# Filter_Board_rev1.net
KiCad netlist of a schematic drawn in EAGLE
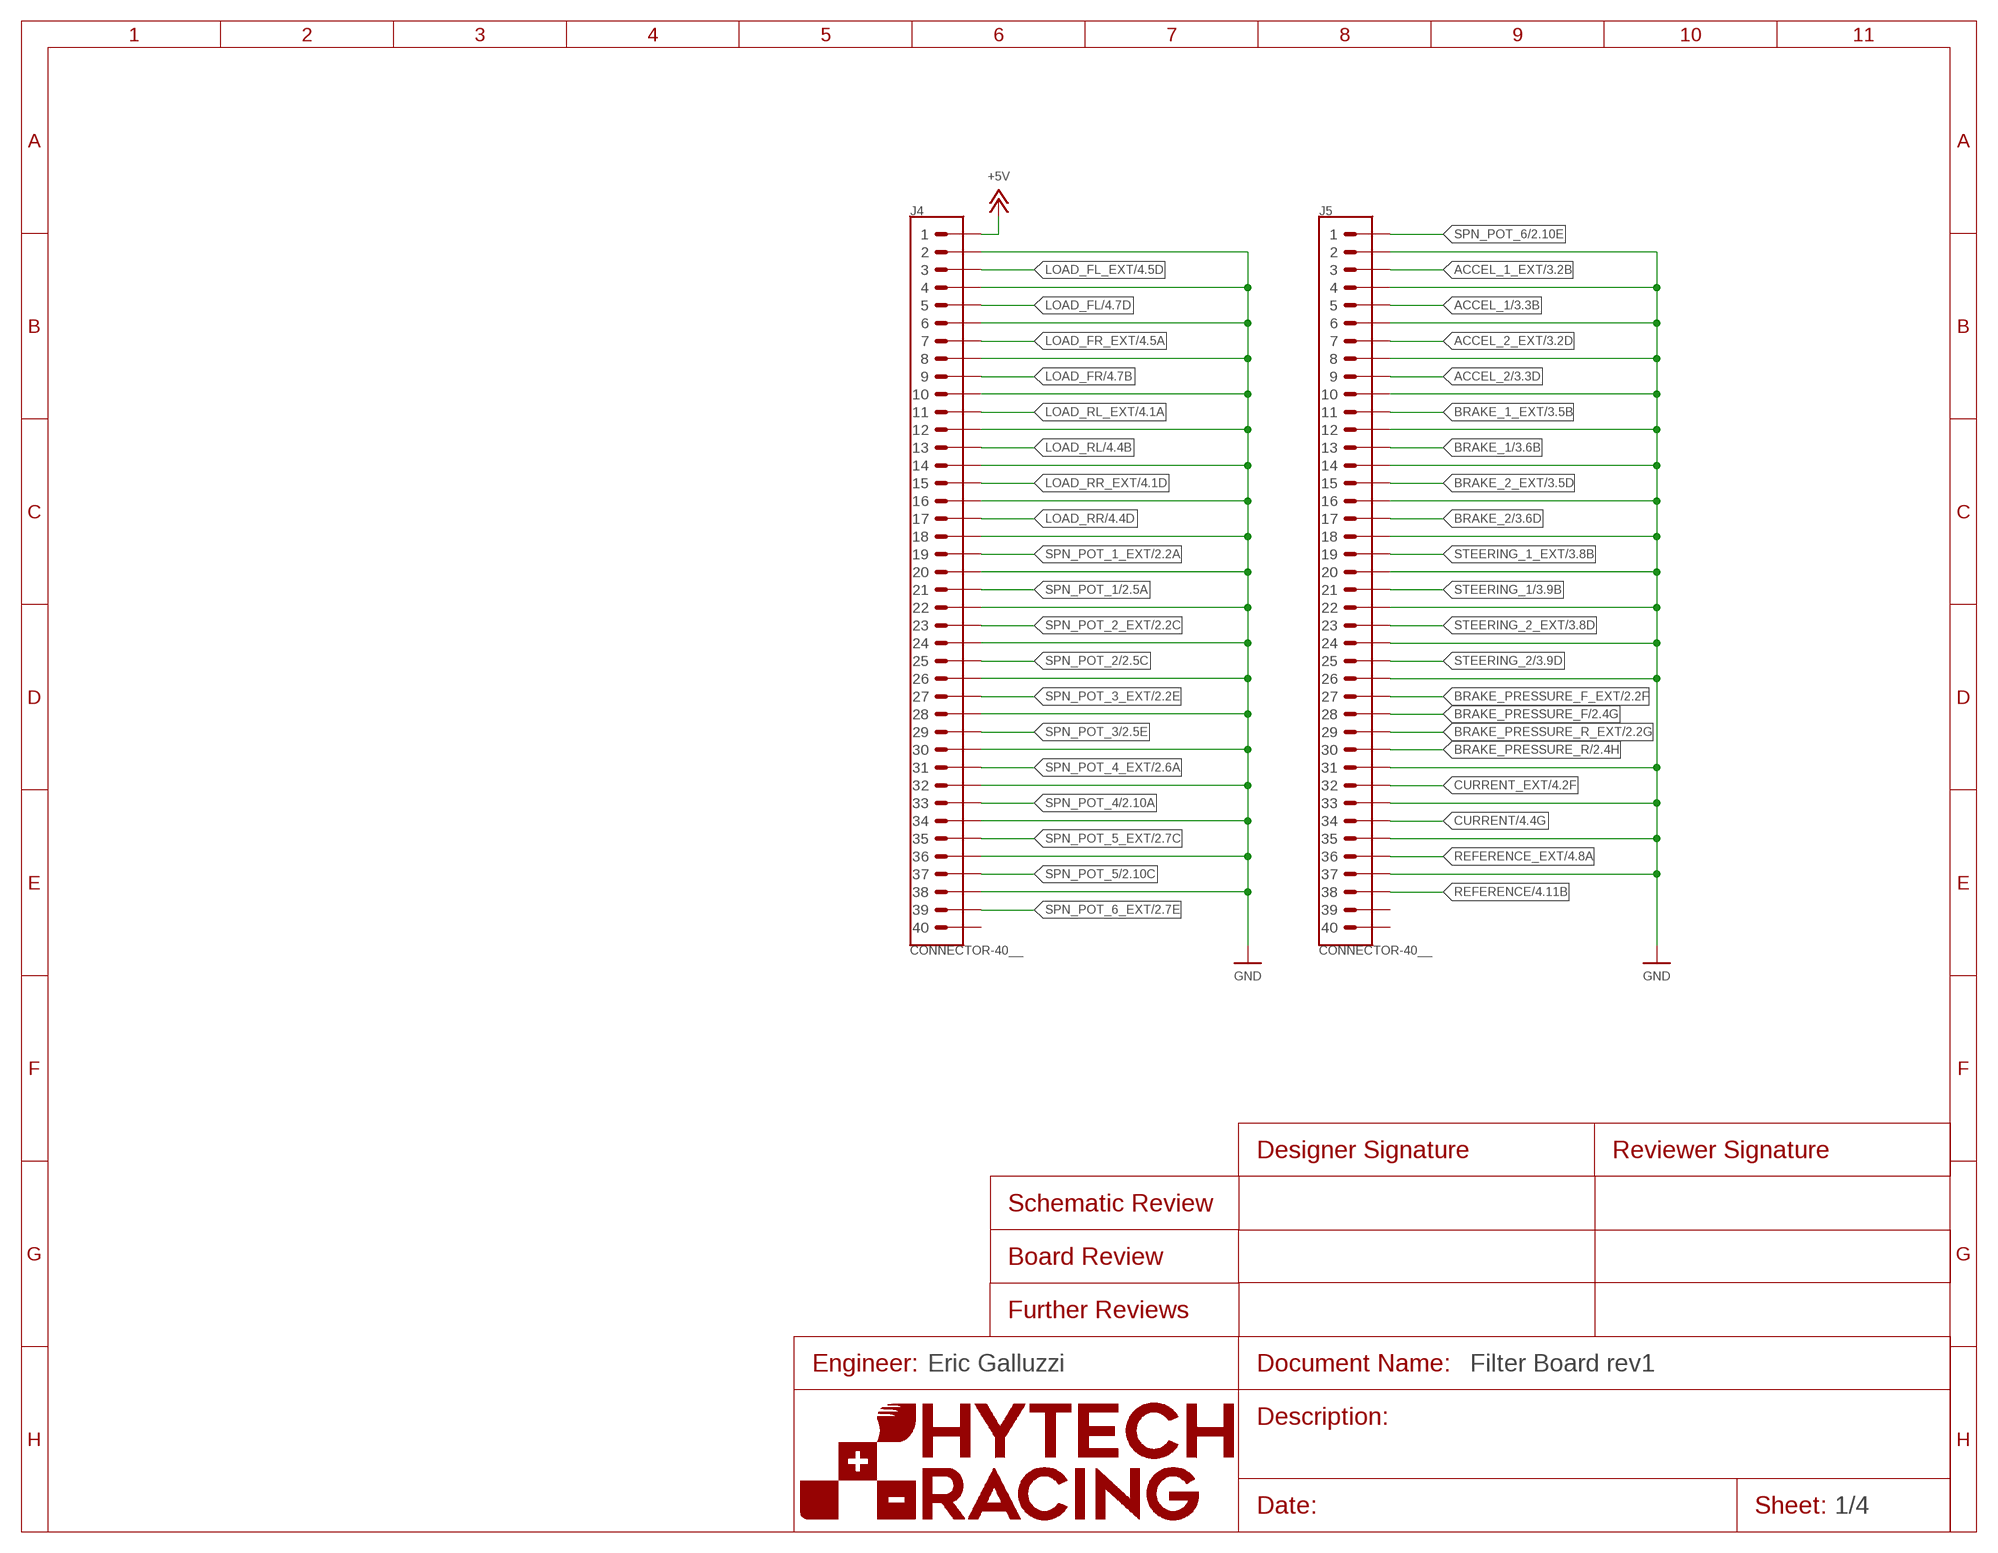
[diagram p0: schematic, sheet 1]
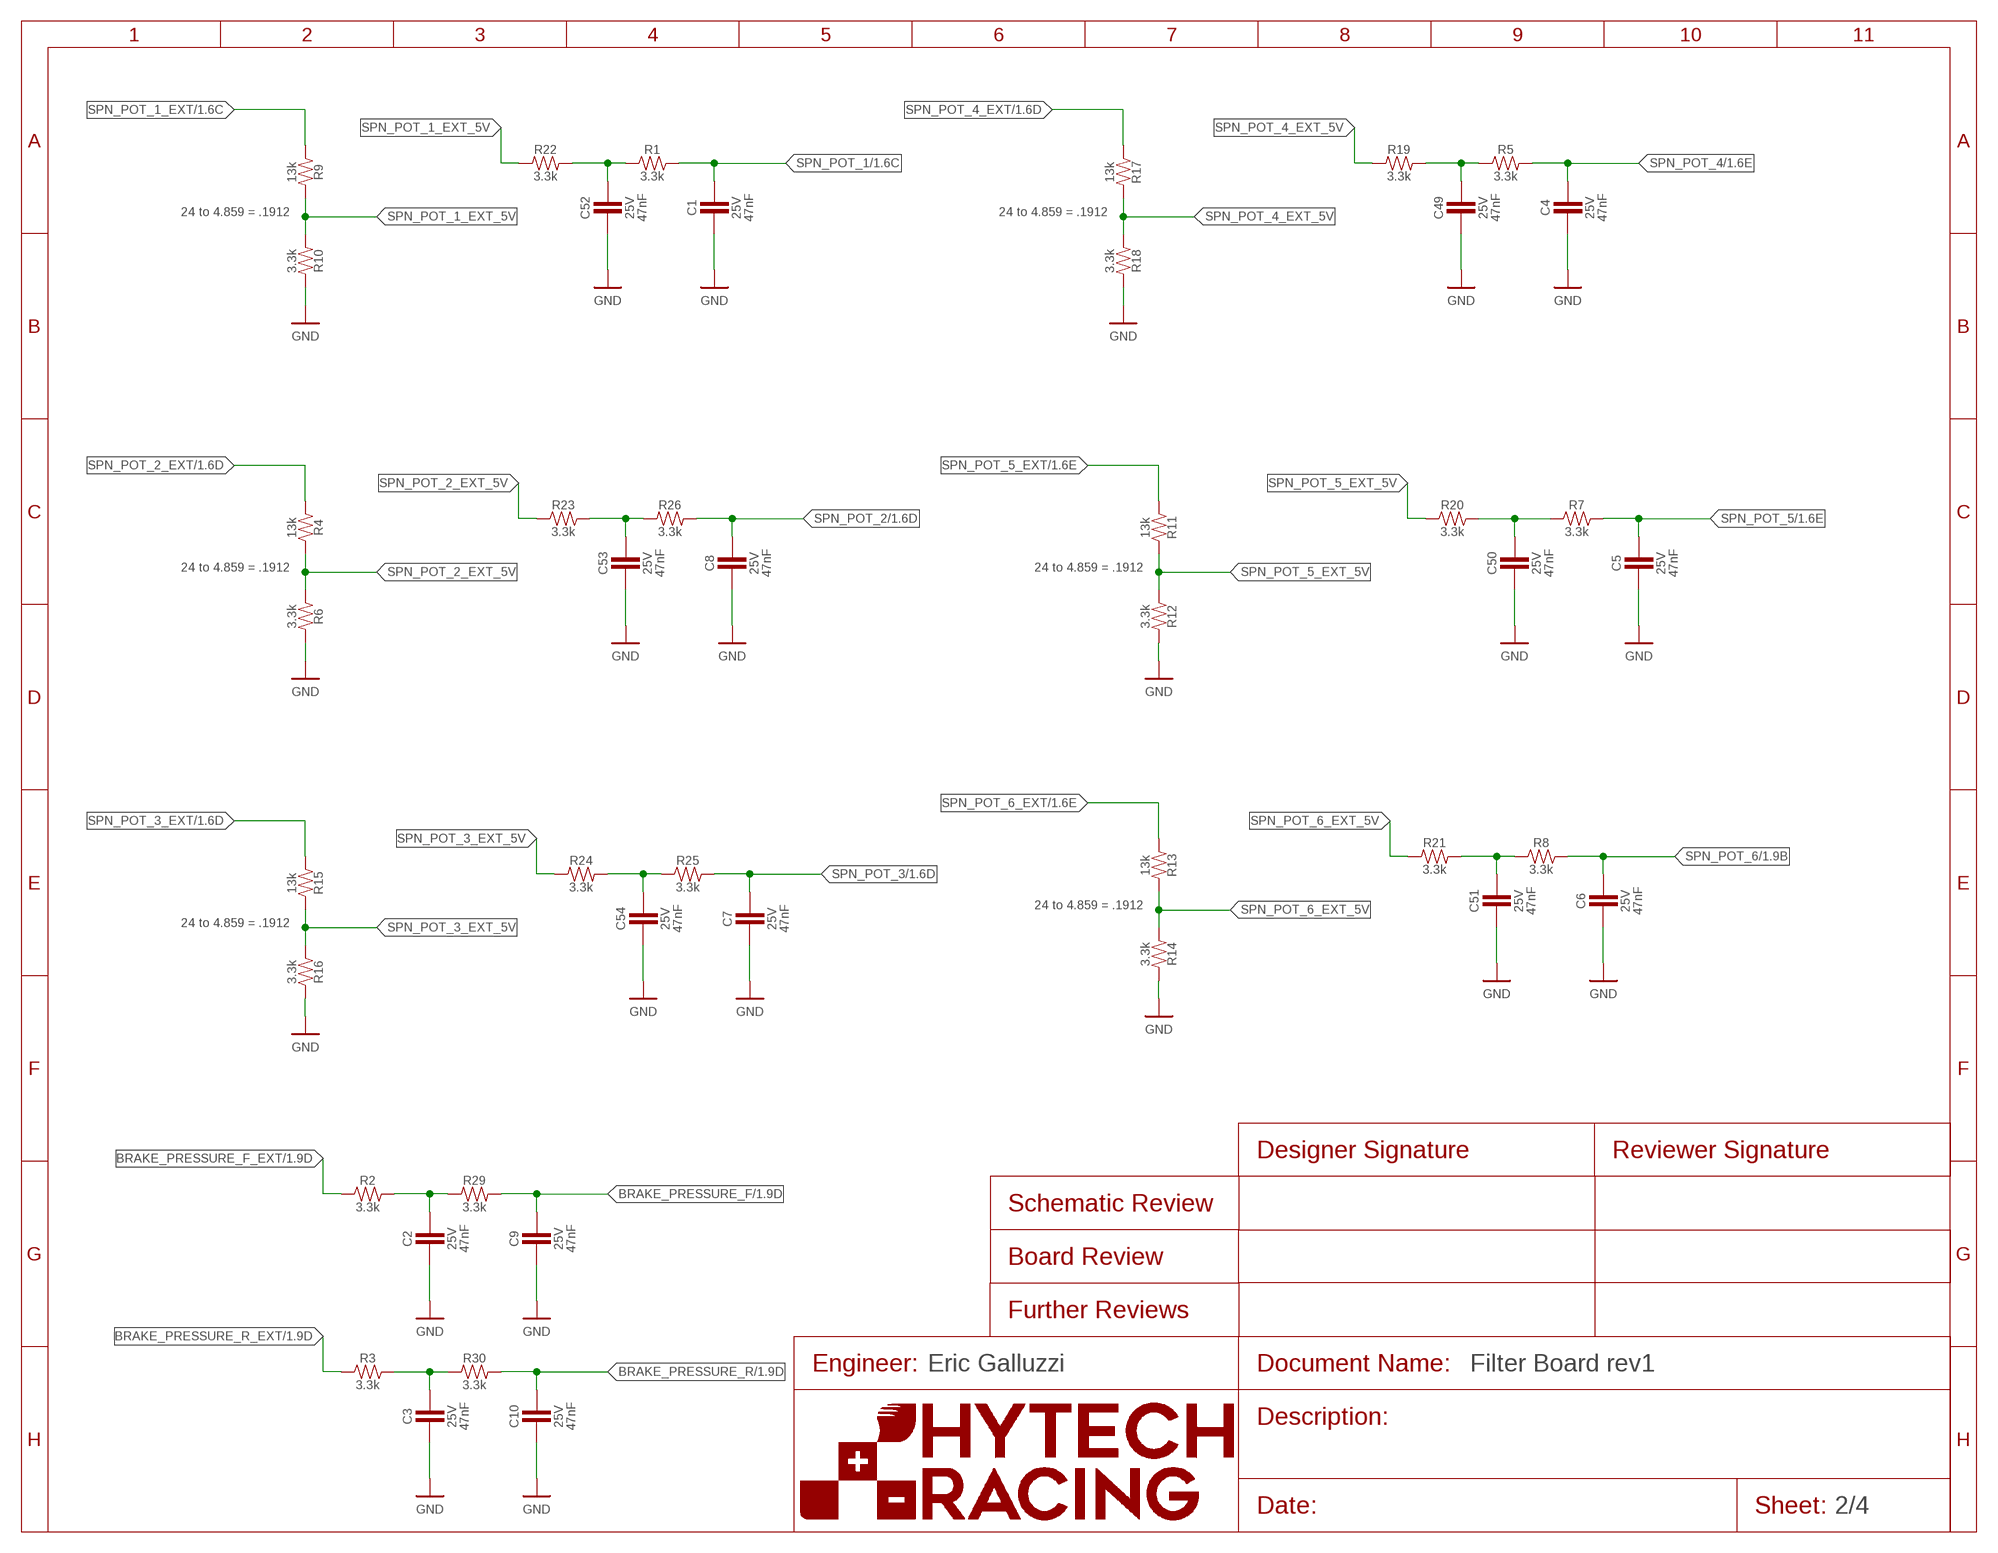
[diagram p1: schematic, sheet 2]
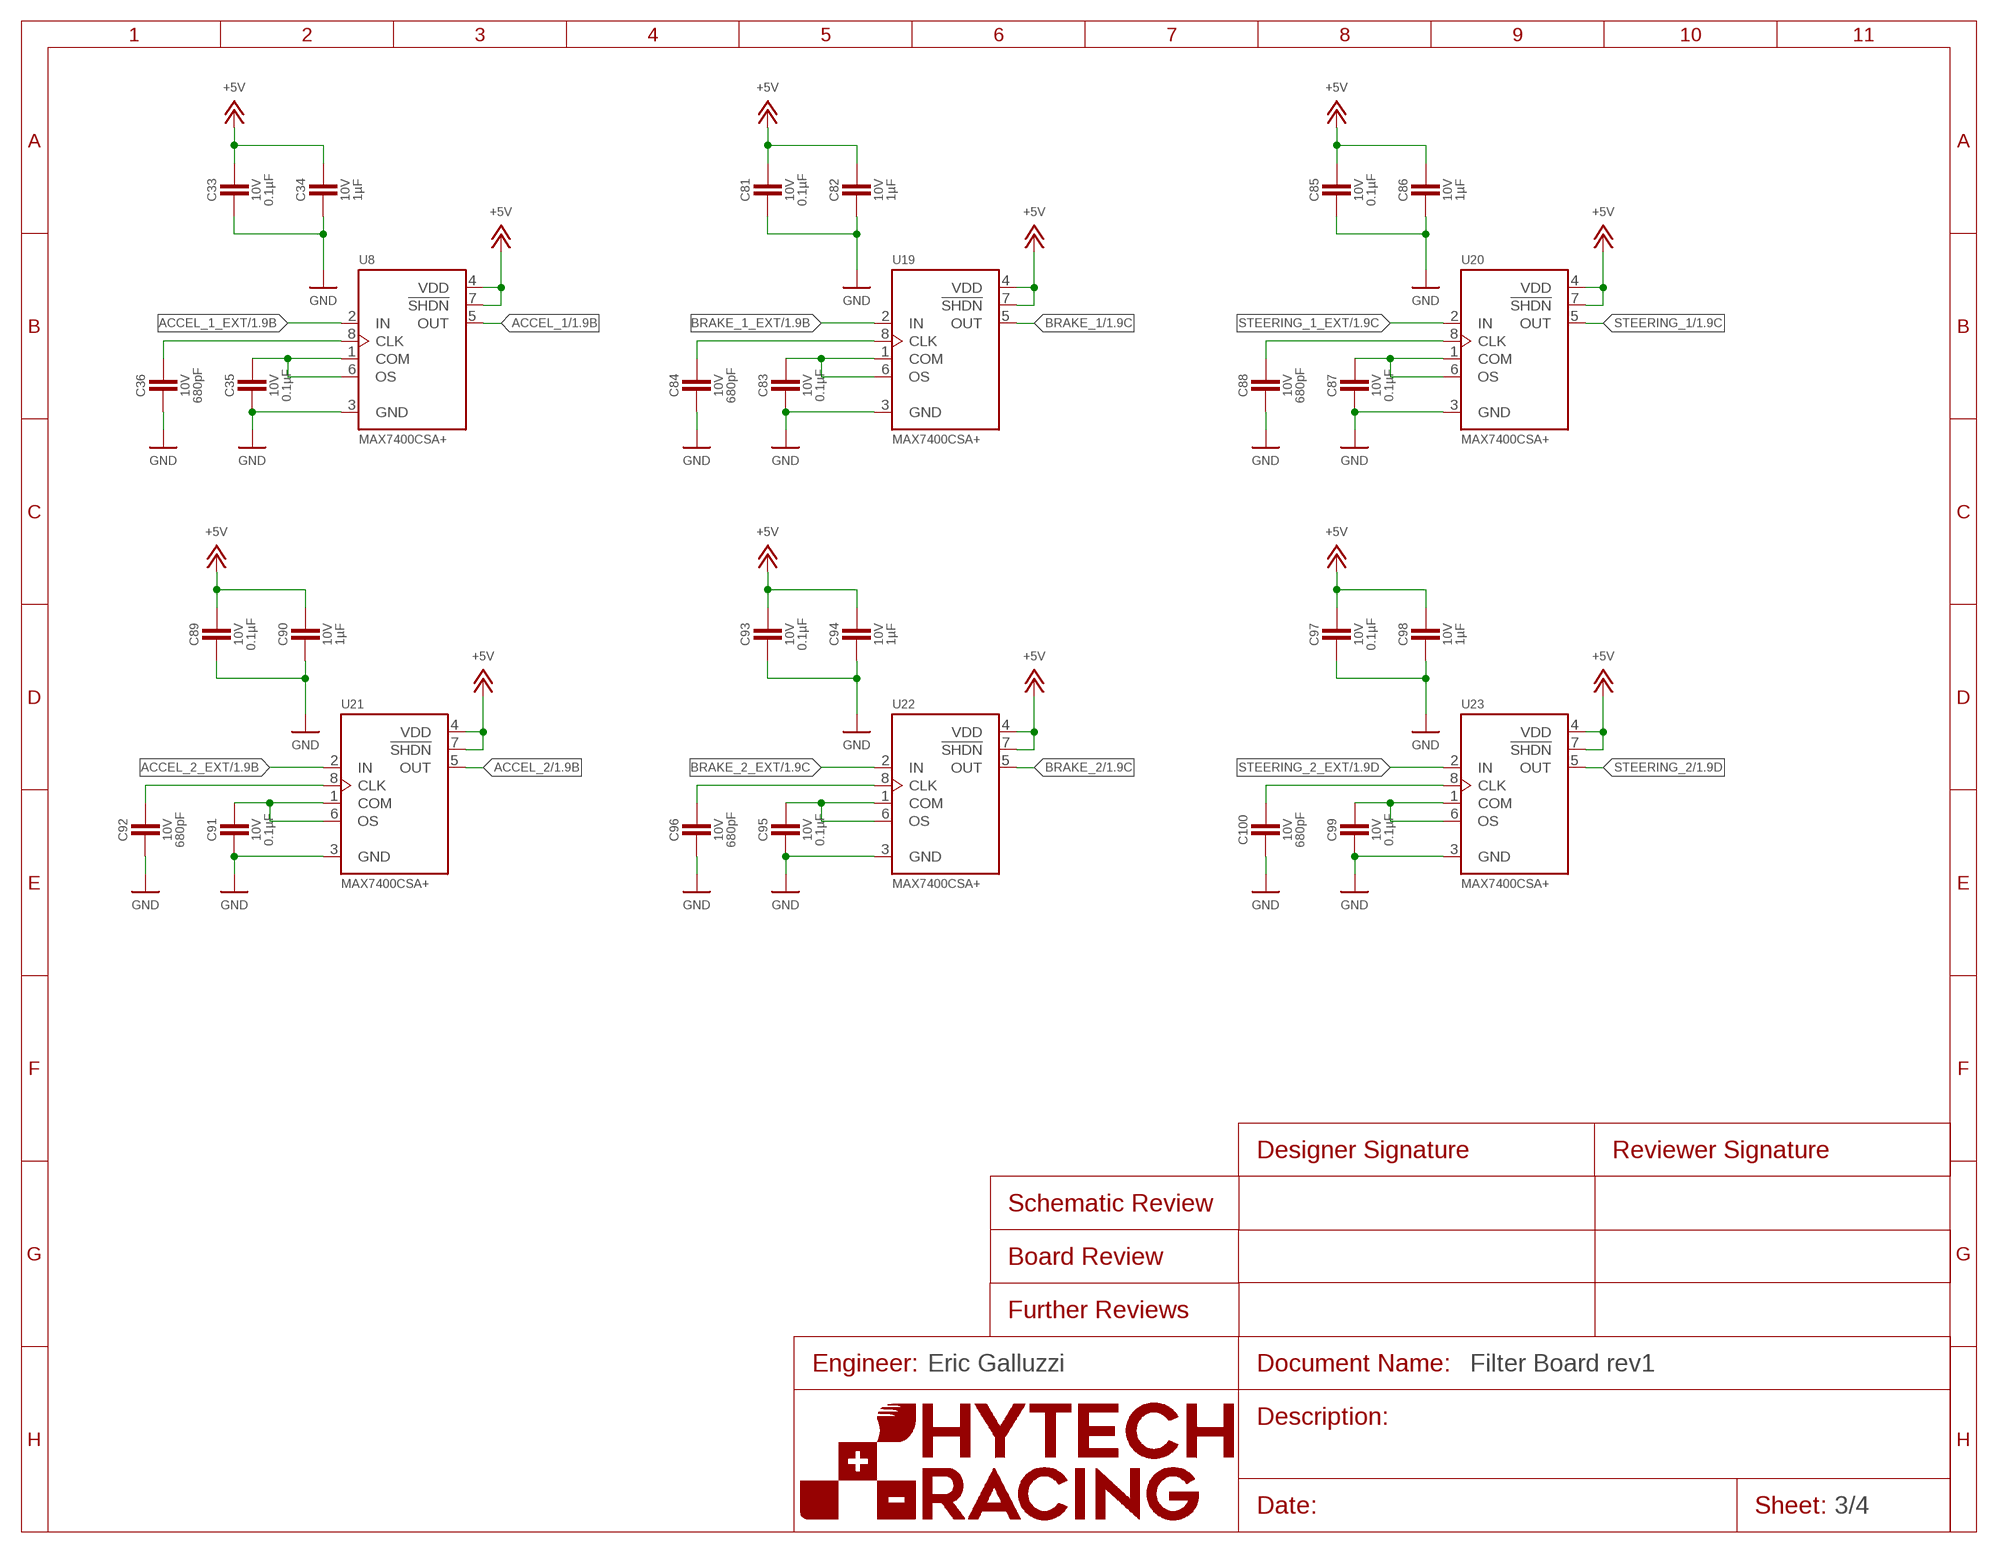
[diagram p2: schematic, sheet 3]
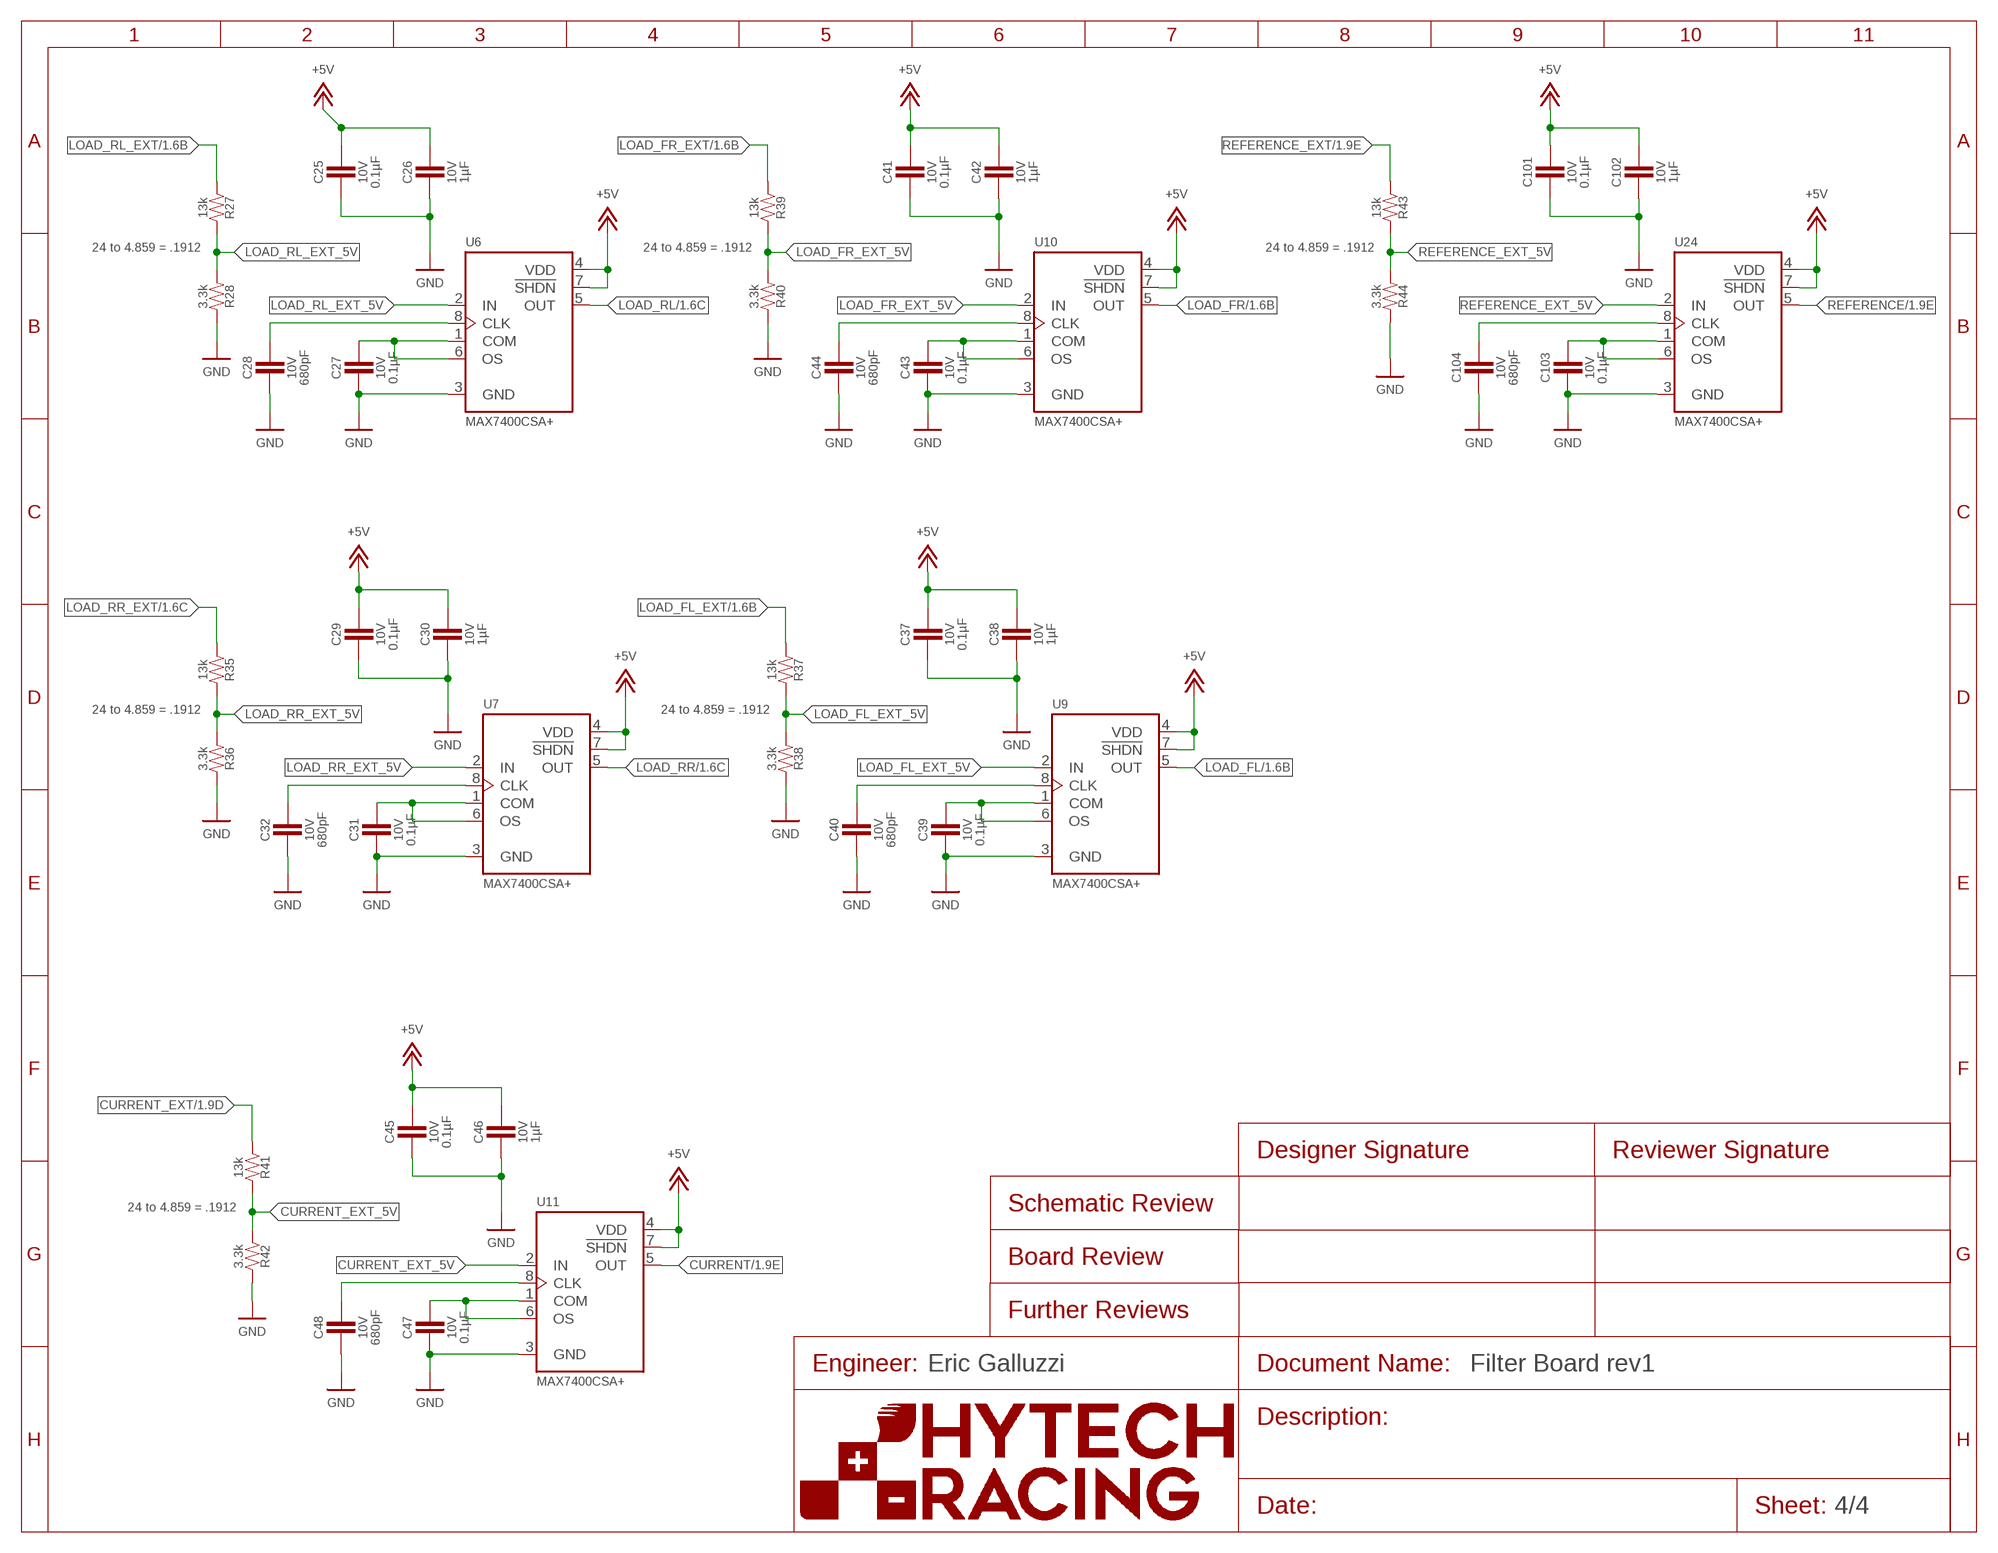
[diagram p3: schematic, sheet 4]

(export (version "E")
  (design (tool "Eeschema 10.0.6"))
  (components
    (comp (ref "C1")
      (value "CAPACITOR_0603_25V_47NF")
      (footprint "eagle-import:0603-CAP")
      (fields
        (field (name "CAPACITANCE") "47nF")
        (field (name "MANUFACTURER") "Kyocera AVX")
        (field (name "MPN") "06033C473K4Z2A")
        (field (name "TOLERANCE") "10%")
        (field (name "VOLTAGE") "25V")
      )
      (libsource (lib "eagle-import") (part "CAPACITOR_?_060325V_47NF"))
    )
    (comp (ref "C2")
      (value "CAPACITOR_0603_25V_47NF")
      (footprint "eagle-import:0603-CAP")
      (fields
        (field (name "CAPACITANCE") "47nF")
        (field (name "MANUFACTURER") "Kyocera AVX")
        (field (name "MPN") "06033C473K4Z2A")
        (field (name "TOLERANCE") "10%")
        (field (name "VOLTAGE") "25V")
      )
      (libsource (lib "eagle-import") (part "CAPACITOR_?_060325V_47NF"))
    )
    (comp (ref "C3")
      (value "CAPACITOR_0603_25V_47NF")
      (footprint "eagle-import:0603-CAP")
      (fields
        (field (name "CAPACITANCE") "47nF")
        (field (name "MANUFACTURER") "Kyocera AVX")
        (field (name "MPN") "06033C473K4Z2A")
        (field (name "TOLERANCE") "10%")
        (field (name "VOLTAGE") "25V")
      )
      (libsource (lib "eagle-import") (part "CAPACITOR_?_060325V_47NF"))
    )
    (comp (ref "C4")
      (value "CAPACITOR_0603_25V_47NF")
      (footprint "eagle-import:0603-CAP")
      (fields
        (field (name "CAPACITANCE") "47nF")
        (field (name "MANUFACTURER") "Kyocera AVX")
        (field (name "MPN") "06033C473K4Z2A")
        (field (name "TOLERANCE") "10%")
        (field (name "VOLTAGE") "25V")
      )
      (libsource (lib "eagle-import") (part "CAPACITOR_?_060325V_47NF"))
    )
    (comp (ref "C5")
      (value "CAPACITOR_0603_25V_47NF")
      (footprint "eagle-import:0603-CAP")
      (fields
        (field (name "CAPACITANCE") "47nF")
        (field (name "MANUFACTURER") "Kyocera AVX")
        (field (name "MPN") "06033C473K4Z2A")
        (field (name "TOLERANCE") "10%")
        (field (name "VOLTAGE") "25V")
      )
      (libsource (lib "eagle-import") (part "CAPACITOR_?_060325V_47NF"))
    )
    (comp (ref "C6")
      (value "CAPACITOR_0603_25V_47NF")
      (footprint "eagle-import:0603-CAP")
      (fields
        (field (name "CAPACITANCE") "47nF")
        (field (name "MANUFACTURER") "Kyocera AVX")
        (field (name "MPN") "06033C473K4Z2A")
        (field (name "TOLERANCE") "10%")
        (field (name "VOLTAGE") "25V")
      )
      (libsource (lib "eagle-import") (part "CAPACITOR_?_060325V_47NF"))
    )
    (comp (ref "C7")
      (value "CAPACITOR_0603_25V_47NF")
      (footprint "eagle-import:0603-CAP")
      (fields
        (field (name "CAPACITANCE") "47nF")
        (field (name "MANUFACTURER") "Kyocera AVX")
        (field (name "MPN") "06033C473K4Z2A")
        (field (name "TOLERANCE") "10%")
        (field (name "VOLTAGE") "25V")
      )
      (libsource (lib "eagle-import") (part "CAPACITOR_?_060325V_47NF"))
    )
    (comp (ref "C8")
      (value "CAPACITOR_0603_25V_47NF")
      (footprint "eagle-import:0603-CAP")
      (fields
        (field (name "CAPACITANCE") "47nF")
        (field (name "MANUFACTURER") "Kyocera AVX")
        (field (name "MPN") "06033C473K4Z2A")
        (field (name "TOLERANCE") "10%")
        (field (name "VOLTAGE") "25V")
      )
      (libsource (lib "eagle-import") (part "CAPACITOR_?_060325V_47NF"))
    )
    (comp (ref "C9")
      (value "CAPACITOR_0603_25V_47NF")
      (footprint "eagle-import:0603-CAP")
      (fields
        (field (name "CAPACITANCE") "47nF")
        (field (name "MANUFACTURER") "Kyocera AVX")
        (field (name "MPN") "06033C473K4Z2A")
        (field (name "TOLERANCE") "10%")
        (field (name "VOLTAGE") "25V")
      )
      (libsource (lib "eagle-import") (part "CAPACITOR_?_060325V_47NF"))
    )
    (comp (ref "C10")
      (value "CAPACITOR_0603_25V_47NF")
      (footprint "eagle-import:0603-CAP")
      (fields
        (field (name "CAPACITANCE") "47nF")
        (field (name "MANUFACTURER") "Kyocera AVX")
        (field (name "MPN") "06033C473K4Z2A")
        (field (name "TOLERANCE") "10%")
        (field (name "VOLTAGE") "25V")
      )
      (libsource (lib "eagle-import") (part "CAPACITOR_?_060325V_47NF"))
    )
    (comp (ref "C49")
      (value "CAPACITOR_0603_25V_47NF")
      (footprint "eagle-import:0603-CAP")
      (fields
        (field (name "CAPACITANCE") "47nF")
        (field (name "MANUFACTURER") "Kyocera AVX")
        (field (name "MPN") "06033C473K4Z2A")
        (field (name "TOLERANCE") "10%")
        (field (name "VOLTAGE") "25V")
      )
      (libsource (lib "eagle-import") (part "CAPACITOR_?_060325V_47NF"))
    )
    (comp (ref "C50")
      (value "CAPACITOR_0603_25V_47NF")
      (footprint "eagle-import:0603-CAP")
      (fields
        (field (name "CAPACITANCE") "47nF")
        (field (name "MANUFACTURER") "Kyocera AVX")
        (field (name "MPN") "06033C473K4Z2A")
        (field (name "TOLERANCE") "10%")
        (field (name "VOLTAGE") "25V")
      )
      (libsource (lib "eagle-import") (part "CAPACITOR_?_060325V_47NF"))
    )
    (comp (ref "C51")
      (value "CAPACITOR_0603_25V_47NF")
      (footprint "eagle-import:0603-CAP")
      (fields
        (field (name "CAPACITANCE") "47nF")
        (field (name "MANUFACTURER") "Kyocera AVX")
        (field (name "MPN") "06033C473K4Z2A")
        (field (name "TOLERANCE") "10%")
        (field (name "VOLTAGE") "25V")
      )
      (libsource (lib "eagle-import") (part "CAPACITOR_?_060325V_47NF"))
    )
    (comp (ref "C52")
      (value "CAPACITOR_0603_25V_47NF")
      (footprint "eagle-import:0603-CAP")
      (fields
        (field (name "CAPACITANCE") "47nF")
        (field (name "MANUFACTURER") "Kyocera AVX")
        (field (name "MPN") "06033C473K4Z2A")
        (field (name "TOLERANCE") "10%")
        (field (name "VOLTAGE") "25V")
      )
      (libsource (lib "eagle-import") (part "CAPACITOR_?_060325V_47NF"))
    )
    (comp (ref "C53")
      (value "CAPACITOR_0603_25V_47NF")
      (footprint "eagle-import:0603-CAP")
      (fields
        (field (name "CAPACITANCE") "47nF")
        (field (name "MANUFACTURER") "Kyocera AVX")
        (field (name "MPN") "06033C473K4Z2A")
        (field (name "TOLERANCE") "10%")
        (field (name "VOLTAGE") "25V")
      )
      (libsource (lib "eagle-import") (part "CAPACITOR_?_060325V_47NF"))
    )
    (comp (ref "C54")
      (value "CAPACITOR_0603_25V_47NF")
      (footprint "eagle-import:0603-CAP")
      (fields
        (field (name "CAPACITANCE") "47nF")
        (field (name "MANUFACTURER") "Kyocera AVX")
        (field (name "MPN") "06033C473K4Z2A")
        (field (name "TOLERANCE") "10%")
        (field (name "VOLTAGE") "25V")
      )
      (libsource (lib "eagle-import") (part "CAPACITOR_?_060325V_47NF"))
    )
    (comp (ref "R1")
      (value "RESISTOR_0603_3.3K")
      (footprint "eagle-import:0603-RES")
      (fields
        (field (name "MANUFACTURER") "Panasonic Electronic Components")
        (field (name "MPN") "ERJ-PB3D3301V")
        (field (name "POWER") "0.2W")
        (field (name "RESISTANCE") "3.3k")
      )
      (libsource (lib "eagle-import") (part "RESISTOR_?_06033.3K"))
    )
    (comp (ref "R2")
      (value "RESISTOR_0603_3.3K")
      (footprint "eagle-import:0603-RES")
      (fields
        (field (name "MANUFACTURER") "Panasonic Electronic Components")
        (field (name "MPN") "ERJ-PB3D3301V")
        (field (name "POWER") "0.2W")
        (field (name "RESISTANCE") "3.3k")
      )
      (libsource (lib "eagle-import") (part "RESISTOR_?_06033.3K"))
    )
    (comp (ref "R3")
      (value "RESISTOR_0603_3.3K")
      (footprint "eagle-import:0603-RES")
      (fields
        (field (name "MANUFACTURER") "Panasonic Electronic Components")
        (field (name "MPN") "ERJ-PB3D3301V")
        (field (name "POWER") "0.2W")
        (field (name "RESISTANCE") "3.3k")
      )
      (libsource (lib "eagle-import") (part "RESISTOR_?_06033.3K"))
    )
    (comp (ref "R4")
      (value "RESISTOR_0603_13K")
      (footprint "eagle-import:0603-RES")
      (fields
        (field (name "MANUFACTURER") "Panasonic Electronic Components")
        (field (name "MPN") "ERA-3ARW133V")
        (field (name "POWER") "0.1W")
        (field (name "RESISTANCE") "13k")
      )
      (libsource (lib "eagle-import") (part "RESISTOR_?_060313K"))
    )
    (comp (ref "R5")
      (value "RESISTOR_0603_3.3K")
      (footprint "eagle-import:0603-RES")
      (fields
        (field (name "MANUFACTURER") "Panasonic Electronic Components")
        (field (name "MPN") "ERJ-PB3D3301V")
        (field (name "POWER") "0.2W")
        (field (name "RESISTANCE") "3.3k")
      )
      (libsource (lib "eagle-import") (part "RESISTOR_?_06033.3K"))
    )
    (comp (ref "R6")
      (value "RESISTOR_0603_3.3K")
      (footprint "eagle-import:0603-RES")
      (fields
        (field (name "MANUFACTURER") "Panasonic Electronic Components")
        (field (name "MPN") "ERJ-PB3D3301V")
        (field (name "POWER") "0.2W")
        (field (name "RESISTANCE") "3.3k")
      )
      (libsource (lib "eagle-import") (part "RESISTOR_?_06033.3K"))
    )
    (comp (ref "R7")
      (value "RESISTOR_0603_3.3K")
      (footprint "eagle-import:0603-RES")
      (fields
        (field (name "MANUFACTURER") "Panasonic Electronic Components")
        (field (name "MPN") "ERJ-PB3D3301V")
        (field (name "POWER") "0.2W")
        (field (name "RESISTANCE") "3.3k")
      )
      (libsource (lib "eagle-import") (part "RESISTOR_?_06033.3K"))
    )
    (comp (ref "R8")
      (value "RESISTOR_0603_3.3K")
      (footprint "eagle-import:0603-RES")
      (fields
        (field (name "MANUFACTURER") "Panasonic Electronic Components")
        (field (name "MPN") "ERJ-PB3D3301V")
        (field (name "POWER") "0.2W")
        (field (name "RESISTANCE") "3.3k")
      )
      (libsource (lib "eagle-import") (part "RESISTOR_?_06033.3K"))
    )
    (comp (ref "R9")
      (value "RESISTOR_0603_13K")
      (footprint "eagle-import:0603-RES")
      (fields
        (field (name "MANUFACTURER") "Panasonic Electronic Components")
        (field (name "MPN") "ERA-3ARW133V")
        (field (name "POWER") "0.1W")
        (field (name "RESISTANCE") "13k")
      )
      (libsource (lib "eagle-import") (part "RESISTOR_?_060313K"))
    )
    (comp (ref "R10")
      (value "RESISTOR_0603_3.3K")
      (footprint "eagle-import:0603-RES")
      (fields
        (field (name "MANUFACTURER") "Panasonic Electronic Components")
        (field (name "MPN") "ERJ-PB3D3301V")
        (field (name "POWER") "0.2W")
        (field (name "RESISTANCE") "3.3k")
      )
      (libsource (lib "eagle-import") (part "RESISTOR_?_06033.3K"))
    )
    (comp (ref "R11")
      (value "RESISTOR_0603_13K")
      (footprint "eagle-import:0603-RES")
      (fields
        (field (name "MANUFACTURER") "Panasonic Electronic Components")
        (field (name "MPN") "ERA-3ARW133V")
        (field (name "POWER") "0.1W")
        (field (name "RESISTANCE") "13k")
      )
      (libsource (lib "eagle-import") (part "RESISTOR_?_060313K"))
    )
    (comp (ref "R12")
      (value "RESISTOR_0603_3.3K")
      (footprint "eagle-import:0603-RES")
      (fields
        (field (name "MANUFACTURER") "Panasonic Electronic Components")
        (field (name "MPN") "ERJ-PB3D3301V")
        (field (name "POWER") "0.2W")
        (field (name "RESISTANCE") "3.3k")
      )
      (libsource (lib "eagle-import") (part "RESISTOR_?_06033.3K"))
    )
    (comp (ref "R13")
      (value "RESISTOR_0603_13K")
      (footprint "eagle-import:0603-RES")
      (fields
        (field (name "MANUFACTURER") "Panasonic Electronic Components")
        (field (name "MPN") "ERA-3ARW133V")
        (field (name "POWER") "0.1W")
        (field (name "RESISTANCE") "13k")
      )
      (libsource (lib "eagle-import") (part "RESISTOR_?_060313K"))
    )
    (comp (ref "R14")
      (value "RESISTOR_0603_3.3K")
      (footprint "eagle-import:0603-RES")
      (fields
        (field (name "MANUFACTURER") "Panasonic Electronic Components")
        (field (name "MPN") "ERJ-PB3D3301V")
        (field (name "POWER") "0.2W")
        (field (name "RESISTANCE") "3.3k")
      )
      (libsource (lib "eagle-import") (part "RESISTOR_?_06033.3K"))
    )
    (comp (ref "R15")
      (value "RESISTOR_0603_13K")
      (footprint "eagle-import:0603-RES")
      (fields
        (field (name "MANUFACTURER") "Panasonic Electronic Components")
        (field (name "MPN") "ERA-3ARW133V")
        (field (name "POWER") "0.1W")
        (field (name "RESISTANCE") "13k")
      )
      (libsource (lib "eagle-import") (part "RESISTOR_?_060313K"))
    )
    (comp (ref "R16")
      (value "RESISTOR_0603_3.3K")
      (footprint "eagle-import:0603-RES")
      (fields
        (field (name "MANUFACTURER") "Panasonic Electronic Components")
        (field (name "MPN") "ERJ-PB3D3301V")
        (field (name "POWER") "0.2W")
        (field (name "RESISTANCE") "3.3k")
      )
      (libsource (lib "eagle-import") (part "RESISTOR_?_06033.3K"))
    )
    (comp (ref "R17")
      (value "RESISTOR_0603_13K")
      (footprint "eagle-import:0603-RES")
      (fields
        (field (name "MANUFACTURER") "Panasonic Electronic Components")
        (field (name "MPN") "ERA-3ARW133V")
        (field (name "POWER") "0.1W")
        (field (name "RESISTANCE") "13k")
      )
      (libsource (lib "eagle-import") (part "RESISTOR_?_060313K"))
    )
    (comp (ref "R18")
      (value "RESISTOR_0603_3.3K")
      (footprint "eagle-import:0603-RES")
      (fields
        (field (name "MANUFACTURER") "Panasonic Electronic Components")
        (field (name "MPN") "ERJ-PB3D3301V")
        (field (name "POWER") "0.2W")
        (field (name "RESISTANCE") "3.3k")
      )
      (libsource (lib "eagle-import") (part "RESISTOR_?_06033.3K"))
    )
    (comp (ref "R19")
      (value "RESISTOR_0603_3.3K")
      (footprint "eagle-import:0603-RES")
      (fields
        (field (name "MANUFACTURER") "Panasonic Electronic Components")
        (field (name "MPN") "ERJ-PB3D3301V")
        (field (name "POWER") "0.2W")
        (field (name "RESISTANCE") "3.3k")
      )
      (libsource (lib "eagle-import") (part "RESISTOR_?_06033.3K"))
    )
    (comp (ref "R20")
      (value "RESISTOR_0603_3.3K")
      (footprint "eagle-import:0603-RES")
      (fields
        (field (name "MANUFACTURER") "Panasonic Electronic Components")
        (field (name "MPN") "ERJ-PB3D3301V")
        (field (name "POWER") "0.2W")
        (field (name "RESISTANCE") "3.3k")
      )
      (libsource (lib "eagle-import") (part "RESISTOR_?_06033.3K"))
    )
    (comp (ref "R21")
      (value "RESISTOR_0603_3.3K")
      (footprint "eagle-import:0603-RES")
      (fields
        (field (name "MANUFACTURER") "Panasonic Electronic Components")
        (field (name "MPN") "ERJ-PB3D3301V")
        (field (name "POWER") "0.2W")
        (field (name "RESISTANCE") "3.3k")
      )
      (libsource (lib "eagle-import") (part "RESISTOR_?_06033.3K"))
    )
    (comp (ref "R22")
      (value "RESISTOR_0603_3.3K")
      (footprint "eagle-import:0603-RES")
      (fields
        (field (name "MANUFACTURER") "Panasonic Electronic Components")
        (field (name "MPN") "ERJ-PB3D3301V")
        (field (name "POWER") "0.2W")
        (field (name "RESISTANCE") "3.3k")
      )
      (libsource (lib "eagle-import") (part "RESISTOR_?_06033.3K"))
    )
    (comp (ref "R23")
      (value "RESISTOR_0603_3.3K")
      (footprint "eagle-import:0603-RES")
      (fields
        (field (name "MANUFACTURER") "Panasonic Electronic Components")
        (field (name "MPN") "ERJ-PB3D3301V")
        (field (name "POWER") "0.2W")
        (field (name "RESISTANCE") "3.3k")
      )
      (libsource (lib "eagle-import") (part "RESISTOR_?_06033.3K"))
    )
    (comp (ref "R24")
      (value "RESISTOR_0603_3.3K")
      (footprint "eagle-import:0603-RES")
      (fields
        (field (name "MANUFACTURER") "Panasonic Electronic Components")
        (field (name "MPN") "ERJ-PB3D3301V")
        (field (name "POWER") "0.2W")
        (field (name "RESISTANCE") "3.3k")
      )
      (libsource (lib "eagle-import") (part "RESISTOR_?_06033.3K"))
    )
    (comp (ref "R25")
      (value "RESISTOR_0603_3.3K")
      (footprint "eagle-import:0603-RES")
      (fields
        (field (name "MANUFACTURER") "Panasonic Electronic Components")
        (field (name "MPN") "ERJ-PB3D3301V")
        (field (name "POWER") "0.2W")
        (field (name "RESISTANCE") "3.3k")
      )
      (libsource (lib "eagle-import") (part "RESISTOR_?_06033.3K"))
    )
    (comp (ref "R26")
      (value "RESISTOR_0603_3.3K")
      (footprint "eagle-import:0603-RES")
      (fields
        (field (name "MANUFACTURER") "Panasonic Electronic Components")
        (field (name "MPN") "ERJ-PB3D3301V")
        (field (name "POWER") "0.2W")
        (field (name "RESISTANCE") "3.3k")
      )
      (libsource (lib "eagle-import") (part "RESISTOR_?_06033.3K"))
    )
    (comp (ref "R29")
      (value "RESISTOR_0603_3.3K")
      (footprint "eagle-import:0603-RES")
      (fields
        (field (name "MANUFACTURER") "Panasonic Electronic Components")
        (field (name "MPN") "ERJ-PB3D3301V")
        (field (name "POWER") "0.2W")
        (field (name "RESISTANCE") "3.3k")
      )
      (libsource (lib "eagle-import") (part "RESISTOR_?_06033.3K"))
    )
    (comp (ref "R30")
      (value "RESISTOR_0603_3.3K")
      (footprint "eagle-import:0603-RES")
      (fields
        (field (name "MANUFACTURER") "Panasonic Electronic Components")
        (field (name "MPN") "ERJ-PB3D3301V")
        (field (name "POWER") "0.2W")
        (field (name "RESISTANCE") "3.3k")
      )
      (libsource (lib "eagle-import") (part "RESISTOR_?_06033.3K"))
    )
    (comp (ref "J4")
      (value "CONNECTOR-40__")
      (footprint "eagle-import:EHT-120-01")
      (fields (field (name "MANUFACTURER") "Samtec") (field (name "MPN") "EHT-120-01-S-D"))
      (libsource (lib "eagle-import") (part "CONNECTOR-40_?_"))
    )
    (comp (ref "J5")
      (value "CONNECTOR-40__")
      (footprint "eagle-import:EHT-120-01")
      (fields (field (name "MANUFACTURER") "Samtec") (field (name "MPN") "EHT-120-01-S-D"))
      (libsource (lib "eagle-import") (part "CONNECTOR-40_?_"))
    )
    (comp (ref "C33")
      (value "CAPACITOR_0603_10V_0.1UF")
      (footprint "eagle-import:0603-CAP")
      (fields
        (field (name "CAPACITANCE") "0.1µF")
        (field (name "MANUFACTURER") "Vishay Vitramon")
        (field (name "MPN") "VJ0603Y104JXQPW1BC")
        (field (name "TOLERANCE") "5%")
        (field (name "VOLTAGE") "10V")
      )
      (libsource (lib "eagle-import") (part "CAPACITOR_?_060310V_0.1UF"))
    )
    (comp (ref "C34")
      (value "CAPACITOR_0603_10V_1UF")
      (footprint "eagle-import:0603-CAP")
      (fields
        (field (name "CAPACITANCE") "1µF")
        (field (name "MANUFACTURER") "Yageo")
        (field (name "MPN") "CC0603KRX7R6BB105")
        (field (name "TOLERANCE") "10%")
        (field (name "VOLTAGE") "10V")
      )
      (libsource (lib "eagle-import") (part "CAPACITOR_?_060310V_1UF"))
    )
    (comp (ref "C35")
      (value "CAPACITOR_0603_10V_0.1UF")
      (footprint "eagle-import:0603-CAP")
      (fields
        (field (name "CAPACITANCE") "0.1µF")
        (field (name "MANUFACTURER") "Vishay Vitramon")
        (field (name "MPN") "VJ0603Y104JXQPW1BC")
        (field (name "TOLERANCE") "5%")
        (field (name "VOLTAGE") "10V")
      )
      (libsource (lib "eagle-import") (part "CAPACITOR_?_060310V_0.1UF"))
    )
    (comp (ref "C36")
      (value "CAPACITOR_0603_10V_680PF")
      (footprint "eagle-import:0603-CAP")
      (fields
        (field (name "CAPACITANCE") "680pF")
        (field (name "MANUFACTURER") "Würth Elektronik")
        (field (name "MPN") "885012006013")
        (field (name "TOLERANCE") "5%")
        (field (name "VOLTAGE") "10V")
      )
      (libsource (lib "eagle-import") (part "CAPACITOR_?_060310V_680PF"))
    )
    (comp (ref "C81")
      (value "CAPACITOR_0603_10V_0.1UF")
      (footprint "eagle-import:0603-CAP")
      (fields
        (field (name "CAPACITANCE") "0.1µF")
        (field (name "MANUFACTURER") "Vishay Vitramon")
        (field (name "MPN") "VJ0603Y104JXQPW1BC")
        (field (name "TOLERANCE") "5%")
        (field (name "VOLTAGE") "10V")
      )
      (libsource (lib "eagle-import") (part "CAPACITOR_?_060310V_0.1UF"))
    )
    (comp (ref "C82")
      (value "CAPACITOR_0603_10V_1UF")
      (footprint "eagle-import:0603-CAP")
      (fields
        (field (name "CAPACITANCE") "1µF")
        (field (name "MANUFACTURER") "Yageo")
        (field (name "MPN") "CC0603KRX7R6BB105")
        (field (name "TOLERANCE") "10%")
        (field (name "VOLTAGE") "10V")
      )
      (libsource (lib "eagle-import") (part "CAPACITOR_?_060310V_1UF"))
    )
    (comp (ref "C83")
      (value "CAPACITOR_0603_10V_0.1UF")
      (footprint "eagle-import:0603-CAP")
      (fields
        (field (name "CAPACITANCE") "0.1µF")
        (field (name "MANUFACTURER") "Vishay Vitramon")
        (field (name "MPN") "VJ0603Y104JXQPW1BC")
        (field (name "TOLERANCE") "5%")
        (field (name "VOLTAGE") "10V")
      )
      (libsource (lib "eagle-import") (part "CAPACITOR_?_060310V_0.1UF"))
    )
    (comp (ref "C84")
      (value "CAPACITOR_0603_10V_680PF")
      (footprint "eagle-import:0603-CAP")
      (fields
        (field (name "CAPACITANCE") "680pF")
        (field (name "MANUFACTURER") "Würth Elektronik")
        (field (name "MPN") "885012006013")
        (field (name "TOLERANCE") "5%")
        (field (name "VOLTAGE") "10V")
      )
      (libsource (lib "eagle-import") (part "CAPACITOR_?_060310V_680PF"))
    )
    (comp (ref "C85")
      (value "CAPACITOR_0603_10V_0.1UF")
      (footprint "eagle-import:0603-CAP")
      (fields
        (field (name "CAPACITANCE") "0.1µF")
        (field (name "MANUFACTURER") "Vishay Vitramon")
        (field (name "MPN") "VJ0603Y104JXQPW1BC")
        (field (name "TOLERANCE") "5%")
        (field (name "VOLTAGE") "10V")
      )
      (libsource (lib "eagle-import") (part "CAPACITOR_?_060310V_0.1UF"))
    )
    (comp (ref "C86")
      (value "CAPACITOR_0603_10V_1UF")
      (footprint "eagle-import:0603-CAP")
      (fields
        (field (name "CAPACITANCE") "1µF")
        (field (name "MANUFACTURER") "Yageo")
        (field (name "MPN") "CC0603KRX7R6BB105")
        (field (name "TOLERANCE") "10%")
        (field (name "VOLTAGE") "10V")
      )
      (libsource (lib "eagle-import") (part "CAPACITOR_?_060310V_1UF"))
    )
    (comp (ref "C87")
      (value "CAPACITOR_0603_10V_0.1UF")
      (footprint "eagle-import:0603-CAP")
      (fields
        (field (name "CAPACITANCE") "0.1µF")
        (field (name "MANUFACTURER") "Vishay Vitramon")
        (field (name "MPN") "VJ0603Y104JXQPW1BC")
        (field (name "TOLERANCE") "5%")
        (field (name "VOLTAGE") "10V")
      )
      (libsource (lib "eagle-import") (part "CAPACITOR_?_060310V_0.1UF"))
    )
    (comp (ref "C88")
      (value "CAPACITOR_0603_10V_680PF")
      (footprint "eagle-import:0603-CAP")
      (fields
        (field (name "CAPACITANCE") "680pF")
        (field (name "MANUFACTURER") "Würth Elektronik")
        (field (name "MPN") "885012006013")
        (field (name "TOLERANCE") "5%")
        (field (name "VOLTAGE") "10V")
      )
      (libsource (lib "eagle-import") (part "CAPACITOR_?_060310V_680PF"))
    )
    (comp (ref "C89")
      (value "CAPACITOR_0603_10V_0.1UF")
      (footprint "eagle-import:0603-CAP")
      (fields
        (field (name "CAPACITANCE") "0.1µF")
        (field (name "MANUFACTURER") "Vishay Vitramon")
        (field (name "MPN") "VJ0603Y104JXQPW1BC")
        (field (name "TOLERANCE") "5%")
        (field (name "VOLTAGE") "10V")
      )
      (libsource (lib "eagle-import") (part "CAPACITOR_?_060310V_0.1UF"))
    )
    (comp (ref "C90")
      (value "CAPACITOR_0603_10V_1UF")
      (footprint "eagle-import:0603-CAP")
      (fields
        (field (name "CAPACITANCE") "1µF")
        (field (name "MANUFACTURER") "Yageo")
        (field (name "MPN") "CC0603KRX7R6BB105")
        (field (name "TOLERANCE") "10%")
        (field (name "VOLTAGE") "10V")
      )
      (libsource (lib "eagle-import") (part "CAPACITOR_?_060310V_1UF"))
    )
    (comp (ref "C91")
      (value "CAPACITOR_0603_10V_0.1UF")
      (footprint "eagle-import:0603-CAP")
      (fields
        (field (name "CAPACITANCE") "0.1µF")
        (field (name "MANUFACTURER") "Vishay Vitramon")
        (field (name "MPN") "VJ0603Y104JXQPW1BC")
        (field (name "TOLERANCE") "5%")
        (field (name "VOLTAGE") "10V")
      )
      (libsource (lib "eagle-import") (part "CAPACITOR_?_060310V_0.1UF"))
    )
    (comp (ref "C92")
      (value "CAPACITOR_0603_10V_680PF")
      (footprint "eagle-import:0603-CAP")
      (fields
        (field (name "CAPACITANCE") "680pF")
        (field (name "MANUFACTURER") "Würth Elektronik")
        (field (name "MPN") "885012006013")
        (field (name "TOLERANCE") "5%")
        (field (name "VOLTAGE") "10V")
      )
      (libsource (lib "eagle-import") (part "CAPACITOR_?_060310V_680PF"))
    )
    (comp (ref "C93")
      (value "CAPACITOR_0603_10V_0.1UF")
      (footprint "eagle-import:0603-CAP")
      (fields
        (field (name "CAPACITANCE") "0.1µF")
        (field (name "MANUFACTURER") "Vishay Vitramon")
        (field (name "MPN") "VJ0603Y104JXQPW1BC")
        (field (name "TOLERANCE") "5%")
        (field (name "VOLTAGE") "10V")
      )
      (libsource (lib "eagle-import") (part "CAPACITOR_?_060310V_0.1UF"))
    )
    (comp (ref "C94")
      (value "CAPACITOR_0603_10V_1UF")
      (footprint "eagle-import:0603-CAP")
      (fields
        (field (name "CAPACITANCE") "1µF")
        (field (name "MANUFACTURER") "Yageo")
        (field (name "MPN") "CC0603KRX7R6BB105")
        (field (name "TOLERANCE") "10%")
        (field (name "VOLTAGE") "10V")
      )
      (libsource (lib "eagle-import") (part "CAPACITOR_?_060310V_1UF"))
    )
    (comp (ref "C95")
      (value "CAPACITOR_0603_10V_0.1UF")
      (footprint "eagle-import:0603-CAP")
      (fields
        (field (name "CAPACITANCE") "0.1µF")
        (field (name "MANUFACTURER") "Vishay Vitramon")
        (field (name "MPN") "VJ0603Y104JXQPW1BC")
        (field (name "TOLERANCE") "5%")
        (field (name "VOLTAGE") "10V")
      )
      (libsource (lib "eagle-import") (part "CAPACITOR_?_060310V_0.1UF"))
    )
    (comp (ref "C96")
      (value "CAPACITOR_0603_10V_680PF")
      (footprint "eagle-import:0603-CAP")
      (fields
        (field (name "CAPACITANCE") "680pF")
        (field (name "MANUFACTURER") "Würth Elektronik")
        (field (name "MPN") "885012006013")
        (field (name "TOLERANCE") "5%")
        (field (name "VOLTAGE") "10V")
      )
      (libsource (lib "eagle-import") (part "CAPACITOR_?_060310V_680PF"))
    )
    (comp (ref "C97")
      (value "CAPACITOR_0603_10V_0.1UF")
      (footprint "eagle-import:0603-CAP")
      (fields
        (field (name "CAPACITANCE") "0.1µF")
        (field (name "MANUFACTURER") "Vishay Vitramon")
        (field (name "MPN") "VJ0603Y104JXQPW1BC")
        (field (name "TOLERANCE") "5%")
        (field (name "VOLTAGE") "10V")
      )
      (libsource (lib "eagle-import") (part "CAPACITOR_?_060310V_0.1UF"))
    )
    (comp (ref "C98")
      (value "CAPACITOR_0603_10V_1UF")
      (footprint "eagle-import:0603-CAP")
      (fields
        (field (name "CAPACITANCE") "1µF")
        (field (name "MANUFACTURER") "Yageo")
        (field (name "MPN") "CC0603KRX7R6BB105")
        (field (name "TOLERANCE") "10%")
        (field (name "VOLTAGE") "10V")
      )
      (libsource (lib "eagle-import") (part "CAPACITOR_?_060310V_1UF"))
    )
    (comp (ref "C99")
      (value "CAPACITOR_0603_10V_0.1UF")
      (footprint "eagle-import:0603-CAP")
      (fields
        (field (name "CAPACITANCE") "0.1µF")
        (field (name "MANUFACTURER") "Vishay Vitramon")
        (field (name "MPN") "VJ0603Y104JXQPW1BC")
        (field (name "TOLERANCE") "5%")
        (field (name "VOLTAGE") "10V")
      )
      (libsource (lib "eagle-import") (part "CAPACITOR_?_060310V_0.1UF"))
    )
    (comp (ref "C100")
      (value "CAPACITOR_0603_10V_680PF")
      (footprint "eagle-import:0603-CAP")
      (fields
        (field (name "CAPACITANCE") "680pF")
        (field (name "MANUFACTURER") "Würth Elektronik")
        (field (name "MPN") "885012006013")
        (field (name "TOLERANCE") "5%")
        (field (name "VOLTAGE") "10V")
      )
      (libsource (lib "eagle-import") (part "CAPACITOR_?_060310V_680PF"))
    )
    (comp (ref "U8")
      (value "MAX7400")
      (footprint "eagle-import:SOIC-08(NARROW,0.15_)")
      (fields (field (name "MANUFACTURER") "Maxim Integrated") (field (name "MPN") "MAX7400CSA+"))
      (libsource (lib "eagle-import") (part "MAX7400"))
    )
    (comp (ref "U19")
      (value "MAX7400")
      (footprint "eagle-import:SOIC-08(NARROW,0.15_)")
      (fields (field (name "MANUFACTURER") "Maxim Integrated") (field (name "MPN") "MAX7400CSA+"))
      (libsource (lib "eagle-import") (part "MAX7400"))
    )
    (comp (ref "U20")
      (value "MAX7400")
      (footprint "eagle-import:SOIC-08(NARROW,0.15_)")
      (fields (field (name "MANUFACTURER") "Maxim Integrated") (field (name "MPN") "MAX7400CSA+"))
      (libsource (lib "eagle-import") (part "MAX7400"))
    )
    (comp (ref "U21")
      (value "MAX7400")
      (footprint "eagle-import:SOIC-08(NARROW,0.15_)")
      (fields (field (name "MANUFACTURER") "Maxim Integrated") (field (name "MPN") "MAX7400CSA+"))
      (libsource (lib "eagle-import") (part "MAX7400"))
    )
    (comp (ref "U22")
      (value "MAX7400")
      (footprint "eagle-import:SOIC-08(NARROW,0.15_)")
      (fields (field (name "MANUFACTURER") "Maxim Integrated") (field (name "MPN") "MAX7400CSA+"))
      (libsource (lib "eagle-import") (part "MAX7400"))
    )
    (comp (ref "U23")
      (value "MAX7400")
      (footprint "eagle-import:SOIC-08(NARROW,0.15_)")
      (fields (field (name "MANUFACTURER") "Maxim Integrated") (field (name "MPN") "MAX7400CSA+"))
      (libsource (lib "eagle-import") (part "MAX7400"))
    )
    (comp (ref "C25")
      (value "CAPACITOR_0603_10V_0.1UF")
      (footprint "eagle-import:0603-CAP")
      (fields
        (field (name "CAPACITANCE") "0.1µF")
        (field (name "MANUFACTURER") "Vishay Vitramon")
        (field (name "MPN") "VJ0603Y104JXQPW1BC")
        (field (name "TOLERANCE") "5%")
        (field (name "VOLTAGE") "10V")
      )
      (libsource (lib "eagle-import") (part "CAPACITOR_?_060310V_0.1UF"))
    )
    (comp (ref "C26")
      (value "CAPACITOR_0603_10V_1UF")
      (footprint "eagle-import:0603-CAP")
      (fields
        (field (name "CAPACITANCE") "1µF")
        (field (name "MANUFACTURER") "Yageo")
        (field (name "MPN") "CC0603KRX7R6BB105")
        (field (name "TOLERANCE") "10%")
        (field (name "VOLTAGE") "10V")
      )
      (libsource (lib "eagle-import") (part "CAPACITOR_?_060310V_1UF"))
    )
    (comp (ref "C27")
      (value "CAPACITOR_0603_10V_0.1UF")
      (footprint "eagle-import:0603-CAP")
      (fields
        (field (name "CAPACITANCE") "0.1µF")
        (field (name "MANUFACTURER") "Vishay Vitramon")
        (field (name "MPN") "VJ0603Y104JXQPW1BC")
        (field (name "TOLERANCE") "5%")
        (field (name "VOLTAGE") "10V")
      )
      (libsource (lib "eagle-import") (part "CAPACITOR_?_060310V_0.1UF"))
    )
    (comp (ref "C28")
      (value "CAPACITOR_0603_10V_680PF")
      (footprint "eagle-import:0603-CAP")
      (fields
        (field (name "CAPACITANCE") "680pF")
        (field (name "MANUFACTURER") "Würth Elektronik")
        (field (name "MPN") "885012006013")
        (field (name "TOLERANCE") "5%")
        (field (name "VOLTAGE") "10V")
      )
      (libsource (lib "eagle-import") (part "CAPACITOR_?_060310V_680PF"))
    )
    (comp (ref "C29")
      (value "CAPACITOR_0603_10V_0.1UF")
      (footprint "eagle-import:0603-CAP")
      (fields
        (field (name "CAPACITANCE") "0.1µF")
        (field (name "MANUFACTURER") "Vishay Vitramon")
        (field (name "MPN") "VJ0603Y104JXQPW1BC")
        (field (name "TOLERANCE") "5%")
        (field (name "VOLTAGE") "10V")
      )
      (libsource (lib "eagle-import") (part "CAPACITOR_?_060310V_0.1UF"))
    )
    (comp (ref "C30")
      (value "CAPACITOR_0603_10V_1UF")
      (footprint "eagle-import:0603-CAP")
      (fields
        (field (name "CAPACITANCE") "1µF")
        (field (name "MANUFACTURER") "Yageo")
        (field (name "MPN") "CC0603KRX7R6BB105")
        (field (name "TOLERANCE") "10%")
        (field (name "VOLTAGE") "10V")
      )
      (libsource (lib "eagle-import") (part "CAPACITOR_?_060310V_1UF"))
    )
    (comp (ref "C31")
      (value "CAPACITOR_0603_10V_0.1UF")
      (footprint "eagle-import:0603-CAP")
      (fields
        (field (name "CAPACITANCE") "0.1µF")
        (field (name "MANUFACTURER") "Vishay Vitramon")
        (field (name "MPN") "VJ0603Y104JXQPW1BC")
        (field (name "TOLERANCE") "5%")
        (field (name "VOLTAGE") "10V")
      )
      (libsource (lib "eagle-import") (part "CAPACITOR_?_060310V_0.1UF"))
    )
    (comp (ref "C32")
      (value "CAPACITOR_0603_10V_680PF")
      (footprint "eagle-import:0603-CAP")
      (fields
        (field (name "CAPACITANCE") "680pF")
        (field (name "MANUFACTURER") "Würth Elektronik")
        (field (name "MPN") "885012006013")
        (field (name "TOLERANCE") "5%")
        (field (name "VOLTAGE") "10V")
      )
      (libsource (lib "eagle-import") (part "CAPACITOR_?_060310V_680PF"))
    )
    (comp (ref "C37")
      (value "CAPACITOR_0603_10V_0.1UF")
      (footprint "eagle-import:0603-CAP")
      (fields
        (field (name "CAPACITANCE") "0.1µF")
        (field (name "MANUFACTURER") "Vishay Vitramon")
        (field (name "MPN") "VJ0603Y104JXQPW1BC")
        (field (name "TOLERANCE") "5%")
        (field (name "VOLTAGE") "10V")
      )
      (libsource (lib "eagle-import") (part "CAPACITOR_?_060310V_0.1UF"))
    )
    (comp (ref "C38")
      (value "CAPACITOR_0603_10V_1UF")
      (footprint "eagle-import:0603-CAP")
      (fields
        (field (name "CAPACITANCE") "1µF")
        (field (name "MANUFACTURER") "Yageo")
        (field (name "MPN") "CC0603KRX7R6BB105")
        (field (name "TOLERANCE") "10%")
        (field (name "VOLTAGE") "10V")
      )
      (libsource (lib "eagle-import") (part "CAPACITOR_?_060310V_1UF"))
    )
    (comp (ref "C39")
      (value "CAPACITOR_0603_10V_0.1UF")
      (footprint "eagle-import:0603-CAP")
      (fields
        (field (name "CAPACITANCE") "0.1µF")
        (field (name "MANUFACTURER") "Vishay Vitramon")
        (field (name "MPN") "VJ0603Y104JXQPW1BC")
        (field (name "TOLERANCE") "5%")
        (field (name "VOLTAGE") "10V")
      )
      (libsource (lib "eagle-import") (part "CAPACITOR_?_060310V_0.1UF"))
    )
    (comp (ref "C40")
      (value "CAPACITOR_0603_10V_680PF")
      (footprint "eagle-import:0603-CAP")
      (fields
        (field (name "CAPACITANCE") "680pF")
        (field (name "MANUFACTURER") "Würth Elektronik")
        (field (name "MPN") "885012006013")
        (field (name "TOLERANCE") "5%")
        (field (name "VOLTAGE") "10V")
      )
      (libsource (lib "eagle-import") (part "CAPACITOR_?_060310V_680PF"))
    )
    (comp (ref "C41")
      (value "CAPACITOR_0603_10V_0.1UF")
      (footprint "eagle-import:0603-CAP")
      (fields
        (field (name "CAPACITANCE") "0.1µF")
        (field (name "MANUFACTURER") "Vishay Vitramon")
        (field (name "MPN") "VJ0603Y104JXQPW1BC")
        (field (name "TOLERANCE") "5%")
        (field (name "VOLTAGE") "10V")
      )
      (libsource (lib "eagle-import") (part "CAPACITOR_?_060310V_0.1UF"))
    )
    (comp (ref "C42")
      (value "CAPACITOR_0603_10V_1UF")
      (footprint "eagle-import:0603-CAP")
      (fields
        (field (name "CAPACITANCE") "1µF")
        (field (name "MANUFACTURER") "Yageo")
        (field (name "MPN") "CC0603KRX7R6BB105")
        (field (name "TOLERANCE") "10%")
        (field (name "VOLTAGE") "10V")
      )
      (libsource (lib "eagle-import") (part "CAPACITOR_?_060310V_1UF"))
    )
    (comp (ref "C43")
      (value "CAPACITOR_0603_10V_0.1UF")
      (footprint "eagle-import:0603-CAP")
      (fields
        (field (name "CAPACITANCE") "0.1µF")
        (field (name "MANUFACTURER") "Vishay Vitramon")
        (field (name "MPN") "VJ0603Y104JXQPW1BC")
        (field (name "TOLERANCE") "5%")
        (field (name "VOLTAGE") "10V")
      )
      (libsource (lib "eagle-import") (part "CAPACITOR_?_060310V_0.1UF"))
    )
    (comp (ref "C44")
      (value "CAPACITOR_0603_10V_680PF")
      (footprint "eagle-import:0603-CAP")
      (fields
        (field (name "CAPACITANCE") "680pF")
        (field (name "MANUFACTURER") "Würth Elektronik")
        (field (name "MPN") "885012006013")
        (field (name "TOLERANCE") "5%")
        (field (name "VOLTAGE") "10V")
      )
      (libsource (lib "eagle-import") (part "CAPACITOR_?_060310V_680PF"))
    )
    (comp (ref "C45")
      (value "CAPACITOR_0603_10V_0.1UF")
      (footprint "eagle-import:0603-CAP")
      (fields
        (field (name "CAPACITANCE") "0.1µF")
        (field (name "MANUFACTURER") "Vishay Vitramon")
        (field (name "MPN") "VJ0603Y104JXQPW1BC")
        (field (name "TOLERANCE") "5%")
        (field (name "VOLTAGE") "10V")
      )
      (libsource (lib "eagle-import") (part "CAPACITOR_?_060310V_0.1UF"))
    )
    (comp (ref "C46")
      (value "CAPACITOR_0603_10V_1UF")
      (footprint "eagle-import:0603-CAP")
      (fields
        (field (name "CAPACITANCE") "1µF")
        (field (name "MANUFACTURER") "Yageo")
        (field (name "MPN") "CC0603KRX7R6BB105")
        (field (name "TOLERANCE") "10%")
        (field (name "VOLTAGE") "10V")
      )
      (libsource (lib "eagle-import") (part "CAPACITOR_?_060310V_1UF"))
    )
    (comp (ref "C47")
      (value "CAPACITOR_0603_10V_0.1UF")
      (footprint "eagle-import:0603-CAP")
      (fields
        (field (name "CAPACITANCE") "0.1µF")
        (field (name "MANUFACTURER") "Vishay Vitramon")
        (field (name "MPN") "VJ0603Y104JXQPW1BC")
        (field (name "TOLERANCE") "5%")
        (field (name "VOLTAGE") "10V")
      )
      (libsource (lib "eagle-import") (part "CAPACITOR_?_060310V_0.1UF"))
    )
    (comp (ref "C48")
      (value "CAPACITOR_0603_10V_680PF")
      (footprint "eagle-import:0603-CAP")
      (fields
        (field (name "CAPACITANCE") "680pF")
        (field (name "MANUFACTURER") "Würth Elektronik")
        (field (name "MPN") "885012006013")
        (field (name "TOLERANCE") "5%")
        (field (name "VOLTAGE") "10V")
      )
      (libsource (lib "eagle-import") (part "CAPACITOR_?_060310V_680PF"))
    )
    (comp (ref "C101")
      (value "CAPACITOR_0603_10V_0.1UF")
      (footprint "eagle-import:0603-CAP")
      (fields
        (field (name "CAPACITANCE") "0.1µF")
        (field (name "MANUFACTURER") "Vishay Vitramon")
        (field (name "MPN") "VJ0603Y104JXQPW1BC")
        (field (name "TOLERANCE") "5%")
        (field (name "VOLTAGE") "10V")
      )
      (libsource (lib "eagle-import") (part "CAPACITOR_?_060310V_0.1UF"))
    )
    (comp (ref "C102")
      (value "CAPACITOR_0603_10V_1UF")
      (footprint "eagle-import:0603-CAP")
      (fields
        (field (name "CAPACITANCE") "1µF")
        (field (name "MANUFACTURER") "Yageo")
        (field (name "MPN") "CC0603KRX7R6BB105")
        (field (name "TOLERANCE") "10%")
        (field (name "VOLTAGE") "10V")
      )
      (libsource (lib "eagle-import") (part "CAPACITOR_?_060310V_1UF"))
    )
    (comp (ref "C103")
      (value "CAPACITOR_0603_10V_0.1UF")
      (footprint "eagle-import:0603-CAP")
      (fields
        (field (name "CAPACITANCE") "0.1µF")
        (field (name "MANUFACTURER") "Vishay Vitramon")
        (field (name "MPN") "VJ0603Y104JXQPW1BC")
        (field (name "TOLERANCE") "5%")
        (field (name "VOLTAGE") "10V")
      )
      (libsource (lib "eagle-import") (part "CAPACITOR_?_060310V_0.1UF"))
    )
    (comp (ref "C104")
      (value "CAPACITOR_0603_10V_680PF")
      (footprint "eagle-import:0603-CAP")
      (fields
        (field (name "CAPACITANCE") "680pF")
        (field (name "MANUFACTURER") "Würth Elektronik")
        (field (name "MPN") "885012006013")
        (field (name "TOLERANCE") "5%")
        (field (name "VOLTAGE") "10V")
      )
      (libsource (lib "eagle-import") (part "CAPACITOR_?_060310V_680PF"))
    )
    (comp (ref "R27")
      (value "RESISTOR_0603_13K")
      (footprint "eagle-import:0603-RES")
      (fields
        (field (name "MANUFACTURER") "Panasonic Electronic Components")
        (field (name "MPN") "ERA-3ARW133V")
        (field (name "POWER") "0.1W")
        (field (name "RESISTANCE") "13k")
      )
      (libsource (lib "eagle-import") (part "RESISTOR_?_060313K"))
    )
    (comp (ref "R28")
      (value "RESISTOR_0603_3.3K")
      (footprint "eagle-import:0603-RES")
      (fields
        (field (name "MANUFACTURER") "Panasonic Electronic Components")
        (field (name "MPN") "ERJ-PB3D3301V")
        (field (name "POWER") "0.2W")
        (field (name "RESISTANCE") "3.3k")
      )
      (libsource (lib "eagle-import") (part "RESISTOR_?_06033.3K"))
    )
    (comp (ref "R35")
      (value "RESISTOR_0603_13K")
      (footprint "eagle-import:0603-RES")
      (fields
        (field (name "MANUFACTURER") "Panasonic Electronic Components")
        (field (name "MPN") "ERA-3ARW133V")
        (field (name "POWER") "0.1W")
        (field (name "RESISTANCE") "13k")
      )
      (libsource (lib "eagle-import") (part "RESISTOR_?_060313K"))
    )
    (comp (ref "R36")
      (value "RESISTOR_0603_3.3K")
      (footprint "eagle-import:0603-RES")
      (fields
        (field (name "MANUFACTURER") "Panasonic Electronic Components")
        (field (name "MPN") "ERJ-PB3D3301V")
        (field (name "POWER") "0.2W")
        (field (name "RESISTANCE") "3.3k")
      )
      (libsource (lib "eagle-import") (part "RESISTOR_?_06033.3K"))
    )
    (comp (ref "R37")
      (value "RESISTOR_0603_13K")
      (footprint "eagle-import:0603-RES")
      (fields
        (field (name "MANUFACTURER") "Panasonic Electronic Components")
        (field (name "MPN") "ERA-3ARW133V")
        (field (name "POWER") "0.1W")
        (field (name "RESISTANCE") "13k")
      )
      (libsource (lib "eagle-import") (part "RESISTOR_?_060313K"))
    )
    (comp (ref "R38")
      (value "RESISTOR_0603_3.3K")
      (footprint "eagle-import:0603-RES")
      (fields
        (field (name "MANUFACTURER") "Panasonic Electronic Components")
        (field (name "MPN") "ERJ-PB3D3301V")
        (field (name "POWER") "0.2W")
        (field (name "RESISTANCE") "3.3k")
      )
      (libsource (lib "eagle-import") (part "RESISTOR_?_06033.3K"))
    )
    (comp (ref "R39")
      (value "RESISTOR_0603_13K")
      (footprint "eagle-import:0603-RES")
      (fields
        (field (name "MANUFACTURER") "Panasonic Electronic Components")
        (field (name "MPN") "ERA-3ARW133V")
        (field (name "POWER") "0.1W")
        (field (name "RESISTANCE") "13k")
      )
      (libsource (lib "eagle-import") (part "RESISTOR_?_060313K"))
    )
    (comp (ref "R40")
      (value "RESISTOR_0603_3.3K")
      (footprint "eagle-import:0603-RES")
      (fields
        (field (name "MANUFACTURER") "Panasonic Electronic Components")
        (field (name "MPN") "ERJ-PB3D3301V")
        (field (name "POWER") "0.2W")
        (field (name "RESISTANCE") "3.3k")
      )
      (libsource (lib "eagle-import") (part "RESISTOR_?_06033.3K"))
    )
    (comp (ref "R41")
      (value "RESISTOR_0603_13K")
      (footprint "eagle-import:0603-RES")
      (fields
        (field (name "MANUFACTURER") "Panasonic Electronic Components")
        (field (name "MPN") "ERA-3ARW133V")
        (field (name "POWER") "0.1W")
        (field (name "RESISTANCE") "13k")
      )
      (libsource (lib "eagle-import") (part "RESISTOR_?_060313K"))
    )
    (comp (ref "R42")
      (value "RESISTOR_0603_3.3K")
      (footprint "eagle-import:0603-RES")
      (fields
        (field (name "MANUFACTURER") "Panasonic Electronic Components")
        (field (name "MPN") "ERJ-PB3D3301V")
        (field (name "POWER") "0.2W")
        (field (name "RESISTANCE") "3.3k")
      )
      (libsource (lib "eagle-import") (part "RESISTOR_?_06033.3K"))
    )
    (comp (ref "R43")
      (value "RESISTOR_0603_13K")
      (footprint "eagle-import:0603-RES")
      (fields
        (field (name "MANUFACTURER") "Panasonic Electronic Components")
        (field (name "MPN") "ERA-3ARW133V")
        (field (name "POWER") "0.1W")
        (field (name "RESISTANCE") "13k")
      )
      (libsource (lib "eagle-import") (part "RESISTOR_?_060313K"))
    )
    (comp (ref "R44")
      (value "RESISTOR_0603_3.3K")
      (footprint "eagle-import:0603-RES")
      (fields
        (field (name "MANUFACTURER") "Panasonic Electronic Components")
        (field (name "MPN") "ERJ-PB3D3301V")
        (field (name "POWER") "0.2W")
        (field (name "RESISTANCE") "3.3k")
      )
      (libsource (lib "eagle-import") (part "RESISTOR_?_06033.3K"))
    )
    (comp (ref "U6")
      (value "MAX7400")
      (footprint "eagle-import:SOIC-08(NARROW,0.15_)")
      (fields (field (name "MANUFACTURER") "Maxim Integrated") (field (name "MPN") "MAX7400CSA+"))
      (libsource (lib "eagle-import") (part "MAX7400"))
    )
    (comp (ref "U7")
      (value "MAX7400")
      (footprint "eagle-import:SOIC-08(NARROW,0.15_)")
      (fields (field (name "MANUFACTURER") "Maxim Integrated") (field (name "MPN") "MAX7400CSA+"))
      (libsource (lib "eagle-import") (part "MAX7400"))
    )
    (comp (ref "U9")
      (value "MAX7400")
      (footprint "eagle-import:SOIC-08(NARROW,0.15_)")
      (fields (field (name "MANUFACTURER") "Maxim Integrated") (field (name "MPN") "MAX7400CSA+"))
      (libsource (lib "eagle-import") (part "MAX7400"))
    )
    (comp (ref "U10")
      (value "MAX7400")
      (footprint "eagle-import:SOIC-08(NARROW,0.15_)")
      (fields (field (name "MANUFACTURER") "Maxim Integrated") (field (name "MPN") "MAX7400CSA+"))
      (libsource (lib "eagle-import") (part "MAX7400"))
    )
    (comp (ref "U11")
      (value "MAX7400")
      (footprint "eagle-import:SOIC-08(NARROW,0.15_)")
      (fields (field (name "MANUFACTURER") "Maxim Integrated") (field (name "MPN") "MAX7400CSA+"))
      (libsource (lib "eagle-import") (part "MAX7400"))
    )
    (comp (ref "U24")
      (value "MAX7400")
      (footprint "eagle-import:SOIC-08(NARROW,0.15_)")
      (fields (field (name "MANUFACTURER") "Maxim Integrated") (field (name "MPN") "MAX7400CSA+"))
      (libsource (lib "eagle-import") (part "MAX7400"))
    )
  )
  (nets
    (net (code "1") (name "+5V") (class "Default")
      (node (ref "C101") (pin "1") (pinfunction "1_1") (pintype "passive"))
      (node (ref "C102") (pin "1") (pinfunction "1_1") (pintype "passive"))
      (node (ref "C25") (pin "1") (pinfunction "1_1") (pintype "passive"))
      (node (ref "C26") (pin "1") (pinfunction "1_1") (pintype "passive"))
      (node (ref "C29") (pin "1") (pinfunction "1_1") (pintype "passive"))
      (node (ref "C30") (pin "1") (pinfunction "1_1") (pintype "passive"))
      (node (ref "C33") (pin "1") (pinfunction "1_1") (pintype "passive"))
      (node (ref "C34") (pin "1") (pinfunction "1_1") (pintype "passive"))
      (node (ref "C37") (pin "1") (pinfunction "1_1") (pintype "passive"))
      (node (ref "C38") (pin "1") (pinfunction "1_1") (pintype "passive"))
      (node (ref "C41") (pin "1") (pinfunction "1_1") (pintype "passive"))
      (node (ref "C42") (pin "1") (pinfunction "1_1") (pintype "passive"))
      (node (ref "C45") (pin "1") (pinfunction "1_1") (pintype "passive"))
      (node (ref "C46") (pin "1") (pinfunction "1_1") (pintype "passive"))
      (node (ref "C81") (pin "1") (pinfunction "1_1") (pintype "passive"))
      (node (ref "C82") (pin "1") (pinfunction "1_1") (pintype "passive"))
      (node (ref "C85") (pin "1") (pinfunction "1_1") (pintype "passive"))
      (node (ref "C86") (pin "1") (pinfunction "1_1") (pintype "passive"))
      (node (ref "C89") (pin "1") (pinfunction "1_1") (pintype "passive"))
      (node (ref "C90") (pin "1") (pinfunction "1_1") (pintype "passive"))
      (node (ref "C93") (pin "1") (pinfunction "1_1") (pintype "passive"))
      (node (ref "C94") (pin "1") (pinfunction "1_1") (pintype "passive"))
      (node (ref "C97") (pin "1") (pinfunction "1_1") (pintype "passive"))
      (node (ref "C98") (pin "1") (pinfunction "1_1") (pintype "passive"))
      (node (ref "J4") (pin "1") (pinfunction "1_1") (pintype "passive"))
      (node (ref "U10") (pin "4") (pinfunction "VDD_4") (pintype "power_in"))
      (node (ref "U10") (pin "7") (pinfunction "~{SHDN}_7") (pintype "input"))
      (node (ref "U11") (pin "4") (pinfunction "VDD_4") (pintype "power_in"))
      (node (ref "U11") (pin "7") (pinfunction "~{SHDN}_7") (pintype "input"))
      (node (ref "U19") (pin "4") (pinfunction "VDD_4") (pintype "power_in"))
      (node (ref "U19") (pin "7") (pinfunction "~{SHDN}_7") (pintype "input"))
      (node (ref "U20") (pin "4") (pinfunction "VDD_4") (pintype "power_in"))
      (node (ref "U20") (pin "7") (pinfunction "~{SHDN}_7") (pintype "input"))
      (node (ref "U21") (pin "4") (pinfunction "VDD_4") (pintype "power_in"))
      (node (ref "U21") (pin "7") (pinfunction "~{SHDN}_7") (pintype "input"))
      (node (ref "U22") (pin "4") (pinfunction "VDD_4") (pintype "power_in"))
      (node (ref "U22") (pin "7") (pinfunction "~{SHDN}_7") (pintype "input"))
      (node (ref "U23") (pin "4") (pinfunction "VDD_4") (pintype "power_in"))
      (node (ref "U23") (pin "7") (pinfunction "~{SHDN}_7") (pintype "input"))
      (node (ref "U24") (pin "4") (pinfunction "VDD_4") (pintype "power_in"))
      (node (ref "U24") (pin "7") (pinfunction "~{SHDN}_7") (pintype "input"))
      (node (ref "U6") (pin "4") (pinfunction "VDD_4") (pintype "power_in"))
      (node (ref "U6") (pin "7") (pinfunction "~{SHDN}_7") (pintype "input"))
      (node (ref "U7") (pin "4") (pinfunction "VDD_4") (pintype "power_in"))
      (node (ref "U7") (pin "7") (pinfunction "~{SHDN}_7") (pintype "input"))
      (node (ref "U8") (pin "4") (pinfunction "VDD_4") (pintype "power_in"))
      (node (ref "U8") (pin "7") (pinfunction "~{SHDN}_7") (pintype "input"))
      (node (ref "U9") (pin "4") (pinfunction "VDD_4") (pintype "power_in"))
      (node (ref "U9") (pin "7") (pinfunction "~{SHDN}_7") (pintype "input"))
    )
    (net (code "2") (name "ACCEL_1") (class "Default")
      (node (ref "J5") (pin "5") (pinfunction "5_5") (pintype "passive"))
      (node (ref "U8") (pin "5") (pinfunction "OUT_5") (pintype "output"))
    )
    (net (code "3") (name "ACCEL_1_EXT") (class "Default")
      (node (ref "J5") (pin "3") (pinfunction "3_3") (pintype "passive"))
      (node (ref "U8") (pin "2") (pinfunction "IN_2") (pintype "input"))
    )
    (net (code "4") (name "ACCEL_2") (class "Default")
      (node (ref "J5") (pin "9") (pinfunction "9_9") (pintype "passive"))
      (node (ref "U21") (pin "5") (pinfunction "OUT_5") (pintype "output"))
    )
    (net (code "5") (name "ACCEL_2_EXT") (class "Default")
      (node (ref "J5") (pin "7") (pinfunction "7_7") (pintype "passive"))
      (node (ref "U21") (pin "2") (pinfunction "IN_2") (pintype "input"))
    )
    (net (code "6") (name "BRAKE_1") (class "Default")
      (node (ref "J5") (pin "13") (pinfunction "13_13") (pintype "passive"))
      (node (ref "U19") (pin "5") (pinfunction "OUT_5") (pintype "output"))
    )
    (net (code "7") (name "BRAKE_1_EXT") (class "Default")
      (node (ref "J5") (pin "11") (pinfunction "11_11") (pintype "passive"))
      (node (ref "U19") (pin "2") (pinfunction "IN_2") (pintype "input"))
    )
    (net (code "8") (name "BRAKE_2") (class "Default")
      (node (ref "J5") (pin "17") (pinfunction "17_17") (pintype "passive"))
      (node (ref "U22") (pin "5") (pinfunction "OUT_5") (pintype "output"))
    )
    (net (code "9") (name "BRAKE_2_EXT") (class "Default")
      (node (ref "J5") (pin "15") (pinfunction "15_15") (pintype "passive"))
      (node (ref "U22") (pin "2") (pinfunction "IN_2") (pintype "input"))
    )
    (net (code "10") (name "BRAKE_PRESSURE_F") (class "Default")
      (node (ref "C9") (pin "1") (pinfunction "1_1") (pintype "passive"))
      (node (ref "J5") (pin "28") (pinfunction "28_28") (pintype "passive"))
      (node (ref "R29") (pin "2") (pinfunction "2_2") (pintype "passive"))
    )
    (net (code "11") (name "BRAKE_PRESSURE_F_EXT") (class "Default")
      (node (ref "J5") (pin "27") (pinfunction "27_27") (pintype "passive"))
      (node (ref "R2") (pin "1") (pinfunction "1_1") (pintype "passive"))
    )
    (net (code "12") (name "BRAKE_PRESSURE_R") (class "Default")
      (node (ref "C10") (pin "1") (pinfunction "1_1") (pintype "passive"))
      (node (ref "J5") (pin "30") (pinfunction "30_30") (pintype "passive"))
      (node (ref "R30") (pin "2") (pinfunction "2_2") (pintype "passive"))
    )
    (net (code "13") (name "BRAKE_PRESSURE_R_EXT") (class "Default")
      (node (ref "J5") (pin "29") (pinfunction "29_29") (pintype "passive"))
      (node (ref "R3") (pin "1") (pinfunction "1_1") (pintype "passive"))
    )
    (net (code "14") (name "CURRENT") (class "Default")
      (node (ref "J5") (pin "34") (pinfunction "34_34") (pintype "passive"))
      (node (ref "U11") (pin "5") (pinfunction "OUT_5") (pintype "output"))
    )
    (net (code "15") (name "CURRENT_EXT") (class "Default")
      (node (ref "J5") (pin "32") (pinfunction "32_32") (pintype "passive"))
      (node (ref "R41") (pin "1") (pinfunction "1_1") (pintype "passive"))
    )
    (net (code "16") (name "CURRENT_EXT_5V") (class "Default")
      (node (ref "R41") (pin "2") (pinfunction "2_2") (pintype "passive"))
      (node (ref "R42") (pin "1") (pinfunction "1_1") (pintype "passive"))
      (node (ref "U11") (pin "2") (pinfunction "IN_2") (pintype "input"))
    )
    (net (code "17") (name "GND") (class "Default")
      (node (ref "C1") (pin "2") (pinfunction "2_2") (pintype "passive"))
      (node (ref "C10") (pin "2") (pinfunction "2_2") (pintype "passive"))
      (node (ref "C100") (pin "2") (pinfunction "2_2") (pintype "passive"))
      (node (ref "C101") (pin "2") (pinfunction "2_2") (pintype "passive"))
      (node (ref "C102") (pin "2") (pinfunction "2_2") (pintype "passive"))
      (node (ref "C103") (pin "2") (pinfunction "2_2") (pintype "passive"))
      (node (ref "C104") (pin "2") (pinfunction "2_2") (pintype "passive"))
      (node (ref "C2") (pin "2") (pinfunction "2_2") (pintype "passive"))
      (node (ref "C25") (pin "2") (pinfunction "2_2") (pintype "passive"))
      (node (ref "C26") (pin "2") (pinfunction "2_2") (pintype "passive"))
      (node (ref "C27") (pin "2") (pinfunction "2_2") (pintype "passive"))
      (node (ref "C28") (pin "2") (pinfunction "2_2") (pintype "passive"))
      (node (ref "C29") (pin "2") (pinfunction "2_2") (pintype "passive"))
      (node (ref "C3") (pin "2") (pinfunction "2_2") (pintype "passive"))
      (node (ref "C30") (pin "2") (pinfunction "2_2") (pintype "passive"))
      (node (ref "C31") (pin "2") (pinfunction "2_2") (pintype "passive"))
      (node (ref "C32") (pin "2") (pinfunction "2_2") (pintype "passive"))
      (node (ref "C33") (pin "2") (pinfunction "2_2") (pintype "passive"))
      (node (ref "C34") (pin "2") (pinfunction "2_2") (pintype "passive"))
      (node (ref "C35") (pin "2") (pinfunction "2_2") (pintype "passive"))
      (node (ref "C36") (pin "2") (pinfunction "2_2") (pintype "passive"))
      (node (ref "C37") (pin "2") (pinfunction "2_2") (pintype "passive"))
      (node (ref "C38") (pin "2") (pinfunction "2_2") (pintype "passive"))
      (node (ref "C39") (pin "2") (pinfunction "2_2") (pintype "passive"))
      (node (ref "C4") (pin "2") (pinfunction "2_2") (pintype "passive"))
      (node (ref "C40") (pin "2") (pinfunction "2_2") (pintype "passive"))
      (node (ref "C41") (pin "2") (pinfunction "2_2") (pintype "passive"))
      (node (ref "C42") (pin "2") (pinfunction "2_2") (pintype "passive"))
      (node (ref "C43") (pin "2") (pinfunction "2_2") (pintype "passive"))
      (node (ref "C44") (pin "2") (pinfunction "2_2") (pintype "passive"))
      (node (ref "C45") (pin "2") (pinfunction "2_2") (pintype "passive"))
      (node (ref "C46") (pin "2") (pinfunction "2_2") (pintype "passive"))
      (node (ref "C47") (pin "2") (pinfunction "2_2") (pintype "passive"))
      (node (ref "C48") (pin "2") (pinfunction "2_2") (pintype "passive"))
      (node (ref "C49") (pin "2") (pinfunction "2_2") (pintype "passive"))
      (node (ref "C5") (pin "2") (pinfunction "2_2") (pintype "passive"))
      (node (ref "C50") (pin "2") (pinfunction "2_2") (pintype "passive"))
      (node (ref "C51") (pin "2") (pinfunction "2_2") (pintype "passive"))
      (node (ref "C52") (pin "2") (pinfunction "2_2") (pintype "passive"))
      (node (ref "C53") (pin "2") (pinfunction "2_2") (pintype "passive"))
      (node (ref "C54") (pin "2") (pinfunction "2_2") (pintype "passive"))
      (node (ref "C6") (pin "2") (pinfunction "2_2") (pintype "passive"))
      (node (ref "C7") (pin "2") (pinfunction "2_2") (pintype "passive"))
      (node (ref "C8") (pin "2") (pinfunction "2_2") (pintype "passive"))
      (node (ref "C81") (pin "2") (pinfunction "2_2") (pintype "passive"))
      (node (ref "C82") (pin "2") (pinfunction "2_2") (pintype "passive"))
      (node (ref "C83") (pin "2") (pinfunction "2_2") (pintype "passive"))
      (node (ref "C84") (pin "2") (pinfunction "2_2") (pintype "passive"))
      (node (ref "C85") (pin "2") (pinfunction "2_2") (pintype "passive"))
      (node (ref "C86") (pin "2") (pinfunction "2_2") (pintype "passive"))
      (node (ref "C87") (pin "2") (pinfunction "2_2") (pintype "passive"))
      (node (ref "C88") (pin "2") (pinfunction "2_2") (pintype "passive"))
      (node (ref "C89") (pin "2") (pinfunction "2_2") (pintype "passive"))
      (node (ref "C9") (pin "2") (pinfunction "2_2") (pintype "passive"))
      (node (ref "C90") (pin "2") (pinfunction "2_2") (pintype "passive"))
      (node (ref "C91") (pin "2") (pinfunction "2_2") (pintype "passive"))
      (node (ref "C92") (pin "2") (pinfunction "2_2") (pintype "passive"))
      (node (ref "C93") (pin "2") (pinfunction "2_2") (pintype "passive"))
      (node (ref "C94") (pin "2") (pinfunction "2_2") (pintype "passive"))
      (node (ref "C95") (pin "2") (pinfunction "2_2") (pintype "passive"))
      (node (ref "C96") (pin "2") (pinfunction "2_2") (pintype "passive"))
      (node (ref "C97") (pin "2") (pinfunction "2_2") (pintype "passive"))
      (node (ref "C98") (pin "2") (pinfunction "2_2") (pintype "passive"))
      (node (ref "C99") (pin "2") (pinfunction "2_2") (pintype "passive"))
      (node (ref "J4") (pin "10") (pinfunction "10_10") (pintype "passive"))
      (node (ref "J4") (pin "12") (pinfunction "12_12") (pintype "passive"))
      (node (ref "J4") (pin "14") (pinfunction "14_14") (pintype "passive"))
      (node (ref "J4") (pin "16") (pinfunction "16_16") (pintype "passive"))
      (node (ref "J4") (pin "18") (pinfunction "18_18") (pintype "passive"))
      (node (ref "J4") (pin "2") (pinfunction "2_2") (pintype "passive"))
      (node (ref "J4") (pin "20") (pinfunction "20_20") (pintype "passive"))
      (node (ref "J4") (pin "22") (pinfunction "22_22") (pintype "passive"))
      (node (ref "J4") (pin "24") (pinfunction "24_24") (pintype "passive"))
      (node (ref "J4") (pin "26") (pinfunction "26_26") (pintype "passive"))
      (node (ref "J4") (pin "28") (pinfunction "28_28") (pintype "passive"))
      (node (ref "J4") (pin "30") (pinfunction "30_30") (pintype "passive"))
      (node (ref "J4") (pin "32") (pinfunction "32_32") (pintype "passive"))
      (node (ref "J4") (pin "34") (pinfunction "34_34") (pintype "passive"))
      (node (ref "J4") (pin "36") (pinfunction "36_36") (pintype "passive"))
      (node (ref "J4") (pin "38") (pinfunction "38_38") (pintype "passive"))
      (node (ref "J4") (pin "4") (pinfunction "4_4") (pintype "passive"))
      (node (ref "J4") (pin "6") (pinfunction "6_6") (pintype "passive"))
      (node (ref "J4") (pin "8") (pinfunction "8_8") (pintype "passive"))
      (node (ref "J5") (pin "10") (pinfunction "10_10") (pintype "passive"))
      (node (ref "J5") (pin "12") (pinfunction "12_12") (pintype "passive"))
      (node (ref "J5") (pin "14") (pinfunction "14_14") (pintype "passive"))
      (node (ref "J5") (pin "16") (pinfunction "16_16") (pintype "passive"))
      (node (ref "J5") (pin "18") (pinfunction "18_18") (pintype "passive"))
      (node (ref "J5") (pin "2") (pinfunction "2_2") (pintype "passive"))
      (node (ref "J5") (pin "20") (pinfunction "20_20") (pintype "passive"))
      (node (ref "J5") (pin "22") (pinfunction "22_22") (pintype "passive"))
      (node (ref "J5") (pin "24") (pinfunction "24_24") (pintype "passive"))
      (node (ref "J5") (pin "26") (pinfunction "26_26") (pintype "passive"))
      (node (ref "J5") (pin "31") (pinfunction "31_31") (pintype "passive"))
      (node (ref "J5") (pin "33") (pinfunction "33_33") (pintype "passive"))
      (node (ref "J5") (pin "35") (pinfunction "35_35") (pintype "passive"))
      (node (ref "J5") (pin "37") (pinfunction "37_37") (pintype "passive"))
      (node (ref "J5") (pin "4") (pinfunction "4_4") (pintype "passive"))
      (node (ref "J5") (pin "6") (pinfunction "6_6") (pintype "passive"))
      (node (ref "J5") (pin "8") (pinfunction "8_8") (pintype "passive"))
      (node (ref "R10") (pin "2") (pinfunction "2_2") (pintype "passive"))
      (node (ref "R12") (pin "2") (pinfunction "2_2") (pintype "passive"))
      (node (ref "R14") (pin "2") (pinfunction "2_2") (pintype "passive"))
      (node (ref "R16") (pin "2") (pinfunction "2_2") (pintype "passive"))
      (node (ref "R18") (pin "2") (pinfunction "2_2") (pintype "passive"))
      (node (ref "R28") (pin "2") (pinfunction "2_2") (pintype "passive"))
      (node (ref "R36") (pin "2") (pinfunction "2_2") (pintype "passive"))
      (node (ref "R38") (pin "2") (pinfunction "2_2") (pintype "passive"))
      (node (ref "R40") (pin "2") (pinfunction "2_2") (pintype "passive"))
      (node (ref "R42") (pin "2") (pinfunction "2_2") (pintype "passive"))
      (node (ref "R44") (pin "2") (pinfunction "2_2") (pintype "passive"))
      (node (ref "R6") (pin "2") (pinfunction "2_2") (pintype "passive"))
      (node (ref "U10") (pin "3") (pinfunction "GND_3") (pintype "power_in"))
      (node (ref "U11") (pin "3") (pinfunction "GND_3") (pintype "power_in"))
      (node (ref "U19") (pin "3") (pinfunction "GND_3") (pintype "power_in"))
      (node (ref "U20") (pin "3") (pinfunction "GND_3") (pintype "power_in"))
      (node (ref "U21") (pin "3") (pinfunction "GND_3") (pintype "power_in"))
      (node (ref "U22") (pin "3") (pinfunction "GND_3") (pintype "power_in"))
      (node (ref "U23") (pin "3") (pinfunction "GND_3") (pintype "power_in"))
      (node (ref "U24") (pin "3") (pinfunction "GND_3") (pintype "power_in"))
      (node (ref "U6") (pin "3") (pinfunction "GND_3") (pintype "power_in"))
      (node (ref "U7") (pin "3") (pinfunction "GND_3") (pintype "power_in"))
      (node (ref "U8") (pin "3") (pinfunction "GND_3") (pintype "power_in"))
      (node (ref "U9") (pin "3") (pinfunction "GND_3") (pintype "power_in"))
    )
    (net (code "18") (name "LOAD_FL") (class "Default")
      (node (ref "J4") (pin "5") (pinfunction "5_5") (pintype "passive"))
      (node (ref "U9") (pin "5") (pinfunction "OUT_5") (pintype "output"))
    )
    (net (code "19") (name "LOAD_FL_EXT") (class "Default")
      (node (ref "J4") (pin "3") (pinfunction "3_3") (pintype "passive"))
      (node (ref "R37") (pin "1") (pinfunction "1_1") (pintype "passive"))
    )
    (net (code "20") (name "LOAD_FL_EXT_5V") (class "Default")
      (node (ref "R37") (pin "2") (pinfunction "2_2") (pintype "passive"))
      (node (ref "R38") (pin "1") (pinfunction "1_1") (pintype "passive"))
      (node (ref "U9") (pin "2") (pinfunction "IN_2") (pintype "input"))
    )
    (net (code "21") (name "LOAD_FR") (class "Default")
      (node (ref "J4") (pin "9") (pinfunction "9_9") (pintype "passive"))
      (node (ref "U10") (pin "5") (pinfunction "OUT_5") (pintype "output"))
    )
    (net (code "22") (name "LOAD_FR_EXT") (class "Default")
      (node (ref "J4") (pin "7") (pinfunction "7_7") (pintype "passive"))
      (node (ref "R39") (pin "1") (pinfunction "1_1") (pintype "passive"))
    )
    (net (code "23") (name "LOAD_FR_EXT_5V") (class "Default")
      (node (ref "R39") (pin "2") (pinfunction "2_2") (pintype "passive"))
      (node (ref "R40") (pin "1") (pinfunction "1_1") (pintype "passive"))
      (node (ref "U10") (pin "2") (pinfunction "IN_2") (pintype "input"))
    )
    (net (code "24") (name "LOAD_RL") (class "Default")
      (node (ref "J4") (pin "13") (pinfunction "13_13") (pintype "passive"))
      (node (ref "U6") (pin "5") (pinfunction "OUT_5") (pintype "output"))
    )
    (net (code "25") (name "LOAD_RL_EXT") (class "Default")
      (node (ref "J4") (pin "11") (pinfunction "11_11") (pintype "passive"))
      (node (ref "R27") (pin "1") (pinfunction "1_1") (pintype "passive"))
    )
    (net (code "26") (name "LOAD_RL_EXT_5V") (class "Default")
      (node (ref "R27") (pin "2") (pinfunction "2_2") (pintype "passive"))
      (node (ref "R28") (pin "1") (pinfunction "1_1") (pintype "passive"))
      (node (ref "U6") (pin "2") (pinfunction "IN_2") (pintype "input"))
    )
    (net (code "27") (name "LOAD_RR") (class "Default")
      (node (ref "J4") (pin "17") (pinfunction "17_17") (pintype "passive"))
      (node (ref "U7") (pin "5") (pinfunction "OUT_5") (pintype "output"))
    )
    (net (code "28") (name "LOAD_RR_EXT") (class "Default")
      (node (ref "J4") (pin "15") (pinfunction "15_15") (pintype "passive"))
      (node (ref "R35") (pin "1") (pinfunction "1_1") (pintype "passive"))
    )
    (net (code "29") (name "LOAD_RR_EXT_5V") (class "Default")
      (node (ref "R35") (pin "2") (pinfunction "2_2") (pintype "passive"))
      (node (ref "R36") (pin "1") (pinfunction "1_1") (pintype "passive"))
      (node (ref "U7") (pin "2") (pinfunction "IN_2") (pintype "input"))
    )
    (net (code "30") (name "Net-(C2-Pad1)") (class "Default")
      (node (ref "C2") (pin "1") (pinfunction "1_1") (pintype "passive"))
      (node (ref "R2") (pin "2") (pinfunction "2_2") (pintype "passive"))
      (node (ref "R29") (pin "1") (pinfunction "1_1") (pintype "passive"))
    )
    (net (code "31") (name "Net-(C3-Pad1)") (class "Default")
      (node (ref "C3") (pin "1") (pinfunction "1_1") (pintype "passive"))
      (node (ref "R3") (pin "2") (pinfunction "2_2") (pintype "passive"))
      (node (ref "R30") (pin "1") (pinfunction "1_1") (pintype "passive"))
    )
    (net (code "32") (name "Net-(C49-Pad1)") (class "Default")
      (node (ref "C49") (pin "1") (pinfunction "1_1") (pintype "passive"))
      (node (ref "R19") (pin "2") (pinfunction "2_2") (pintype "passive"))
      (node (ref "R5") (pin "1") (pinfunction "1_1") (pintype "passive"))
    )
    (net (code "33") (name "Net-(C50-Pad1)") (class "Default")
      (node (ref "C50") (pin "1") (pinfunction "1_1") (pintype "passive"))
      (node (ref "R20") (pin "2") (pinfunction "2_2") (pintype "passive"))
      (node (ref "R7") (pin "1") (pinfunction "1_1") (pintype "passive"))
    )
    (net (code "34") (name "Net-(C51-Pad1)") (class "Default")
      (node (ref "C51") (pin "1") (pinfunction "1_1") (pintype "passive"))
      (node (ref "R21") (pin "2") (pinfunction "2_2") (pintype "passive"))
      (node (ref "R8") (pin "1") (pinfunction "1_1") (pintype "passive"))
    )
    (net (code "35") (name "Net-(C52-Pad1)") (class "Default")
      (node (ref "C52") (pin "1") (pinfunction "1_1") (pintype "passive"))
      (node (ref "R1") (pin "1") (pinfunction "1_1") (pintype "passive"))
      (node (ref "R22") (pin "2") (pinfunction "2_2") (pintype "passive"))
    )
    (net (code "36") (name "Net-(C53-Pad1)") (class "Default")
      (node (ref "C53") (pin "1") (pinfunction "1_1") (pintype "passive"))
      (node (ref "R23") (pin "2") (pinfunction "2_2") (pintype "passive"))
      (node (ref "R26") (pin "1") (pinfunction "1_1") (pintype "passive"))
    )
    (net (code "37") (name "Net-(C54-Pad1)") (class "Default")
      (node (ref "C54") (pin "1") (pinfunction "1_1") (pintype "passive"))
      (node (ref "R24") (pin "2") (pinfunction "2_2") (pintype "passive"))
      (node (ref "R25") (pin "1") (pinfunction "1_1") (pintype "passive"))
    )
    (net (code "38") (name "Net-(U6-CLK)") (class "Default")
      (node (ref "C28") (pin "1") (pinfunction "1_1") (pintype "passive"))
      (node (ref "U6") (pin "8") (pinfunction "CLK_8") (pintype "input"))
    )
    (net (code "39") (name "Net-(U6-COM)") (class "Default")
      (node (ref "C27") (pin "1") (pinfunction "1_1") (pintype "passive"))
      (node (ref "U6") (pin "1") (pinfunction "COM_1") (pintype "bidirectional"))
      (node (ref "U6") (pin "6") (pinfunction "OS_6") (pintype "bidirectional"))
    )
    (net (code "40") (name "Net-(U7-CLK)") (class "Default")
      (node (ref "C32") (pin "1") (pinfunction "1_1") (pintype "passive"))
      (node (ref "U7") (pin "8") (pinfunction "CLK_8") (pintype "input"))
    )
    (net (code "41") (name "Net-(U7-COM)") (class "Default")
      (node (ref "C31") (pin "1") (pinfunction "1_1") (pintype "passive"))
      (node (ref "U7") (pin "1") (pinfunction "COM_1") (pintype "bidirectional"))
      (node (ref "U7") (pin "6") (pinfunction "OS_6") (pintype "bidirectional"))
    )
    (net (code "42") (name "Net-(U8-CLK)") (class "Default")
      (node (ref "C36") (pin "1") (pinfunction "1_1") (pintype "passive"))
      (node (ref "U8") (pin "8") (pinfunction "CLK_8") (pintype "input"))
    )
    (net (code "43") (name "Net-(U8-COM)") (class "Default")
      (node (ref "C35") (pin "1") (pinfunction "1_1") (pintype "passive"))
      (node (ref "U8") (pin "1") (pinfunction "COM_1") (pintype "bidirectional"))
      (node (ref "U8") (pin "6") (pinfunction "OS_6") (pintype "bidirectional"))
    )
    (net (code "44") (name "Net-(U9-CLK)") (class "Default")
      (node (ref "C40") (pin "1") (pinfunction "1_1") (pintype "passive"))
      (node (ref "U9") (pin "8") (pinfunction "CLK_8") (pintype "input"))
    )
    (net (code "45") (name "Net-(U9-COM)") (class "Default")
      (node (ref "C39") (pin "1") (pinfunction "1_1") (pintype "passive"))
      (node (ref "U9") (pin "1") (pinfunction "COM_1") (pintype "bidirectional"))
      (node (ref "U9") (pin "6") (pinfunction "OS_6") (pintype "bidirectional"))
    )
    (net (code "46") (name "Net-(U10-CLK)") (class "Default")
      (node (ref "C44") (pin "1") (pinfunction "1_1") (pintype "passive"))
      (node (ref "U10") (pin "8") (pinfunction "CLK_8") (pintype "input"))
    )
    (net (code "47") (name "Net-(U10-COM)") (class "Default")
      (node (ref "C43") (pin "1") (pinfunction "1_1") (pintype "passive"))
      (node (ref "U10") (pin "1") (pinfunction "COM_1") (pintype "bidirectional"))
      (node (ref "U10") (pin "6") (pinfunction "OS_6") (pintype "bidirectional"))
    )
    (net (code "48") (name "Net-(U11-CLK)") (class "Default")
      (node (ref "C48") (pin "1") (pinfunction "1_1") (pintype "passive"))
      (node (ref "U11") (pin "8") (pinfunction "CLK_8") (pintype "input"))
    )
    (net (code "49") (name "Net-(U11-COM)") (class "Default")
      (node (ref "C47") (pin "1") (pinfunction "1_1") (pintype "passive"))
      (node (ref "U11") (pin "1") (pinfunction "COM_1") (pintype "bidirectional"))
      (node (ref "U11") (pin "6") (pinfunction "OS_6") (pintype "bidirectional"))
    )
    (net (code "50") (name "Net-(U19-CLK)") (class "Default")
      (node (ref "C84") (pin "1") (pinfunction "1_1") (pintype "passive"))
      (node (ref "U19") (pin "8") (pinfunction "CLK_8") (pintype "input"))
    )
    (net (code "51") (name "Net-(U19-COM)") (class "Default")
      (node (ref "C83") (pin "1") (pinfunction "1_1") (pintype "passive"))
      (node (ref "U19") (pin "1") (pinfunction "COM_1") (pintype "bidirectional"))
      (node (ref "U19") (pin "6") (pinfunction "OS_6") (pintype "bidirectional"))
    )
    (net (code "52") (name "Net-(U20-CLK)") (class "Default")
      (node (ref "C88") (pin "1") (pinfunction "1_1") (pintype "passive"))
      (node (ref "U20") (pin "8") (pinfunction "CLK_8") (pintype "input"))
    )
    (net (code "53") (name "Net-(U20-COM)") (class "Default")
      (node (ref "C87") (pin "1") (pinfunction "1_1") (pintype "passive"))
      (node (ref "U20") (pin "1") (pinfunction "COM_1") (pintype "bidirectional"))
      (node (ref "U20") (pin "6") (pinfunction "OS_6") (pintype "bidirectional"))
    )
    (net (code "54") (name "Net-(U21-CLK)") (class "Default")
      (node (ref "C92") (pin "1") (pinfunction "1_1") (pintype "passive"))
      (node (ref "U21") (pin "8") (pinfunction "CLK_8") (pintype "input"))
    )
    (net (code "55") (name "Net-(U21-COM)") (class "Default")
      (node (ref "C91") (pin "1") (pinfunction "1_1") (pintype "passive"))
      (node (ref "U21") (pin "1") (pinfunction "COM_1") (pintype "bidirectional"))
      (node (ref "U21") (pin "6") (pinfunction "OS_6") (pintype "bidirectional"))
    )
    (net (code "56") (name "Net-(U22-CLK)") (class "Default")
      (node (ref "C96") (pin "1") (pinfunction "1_1") (pintype "passive"))
      (node (ref "U22") (pin "8") (pinfunction "CLK_8") (pintype "input"))
    )
    (net (code "57") (name "Net-(U22-COM)") (class "Default")
      (node (ref "C95") (pin "1") (pinfunction "1_1") (pintype "passive"))
      (node (ref "U22") (pin "1") (pinfunction "COM_1") (pintype "bidirectional"))
      (node (ref "U22") (pin "6") (pinfunction "OS_6") (pintype "bidirectional"))
    )
    (net (code "58") (name "Net-(U23-CLK)") (class "Default")
      (node (ref "C100") (pin "1") (pinfunction "1_1") (pintype "passive"))
      (node (ref "U23") (pin "8") (pinfunction "CLK_8") (pintype "input"))
    )
    (net (code "59") (name "Net-(U23-COM)") (class "Default")
      (node (ref "C99") (pin "1") (pinfunction "1_1") (pintype "passive"))
      (node (ref "U23") (pin "1") (pinfunction "COM_1") (pintype "bidirectional"))
      (node (ref "U23") (pin "6") (pinfunction "OS_6") (pintype "bidirectional"))
    )
    (net (code "60") (name "Net-(U24-CLK)") (class "Default")
      (node (ref "C104") (pin "1") (pinfunction "1_1") (pintype "passive"))
      (node (ref "U24") (pin "8") (pinfunction "CLK_8") (pintype "input"))
    )
    (net (code "61") (name "Net-(U24-COM)") (class "Default")
      (node (ref "C103") (pin "1") (pinfunction "1_1") (pintype "passive"))
      (node (ref "U24") (pin "1") (pinfunction "COM_1") (pintype "bidirectional"))
      (node (ref "U24") (pin "6") (pinfunction "OS_6") (pintype "bidirectional"))
    )
    (net (code "62") (name "REFERENCE") (class "Default")
      (node (ref "J5") (pin "38") (pinfunction "38_38") (pintype "passive"))
      (node (ref "U24") (pin "5") (pinfunction "OUT_5") (pintype "output"))
    )
    (net (code "63") (name "REFERENCE_EXT") (class "Default")
      (node (ref "J5") (pin "36") (pinfunction "36_36") (pintype "passive"))
      (node (ref "R43") (pin "1") (pinfunction "1_1") (pintype "passive"))
    )
    (net (code "64") (name "REFERENCE_EXT_5V") (class "Default")
      (node (ref "R43") (pin "2") (pinfunction "2_2") (pintype "passive"))
      (node (ref "R44") (pin "1") (pinfunction "1_1") (pintype "passive"))
      (node (ref "U24") (pin "2") (pinfunction "IN_2") (pintype "input"))
    )
    (net (code "65") (name "SPN_POT_1") (class "Default")
      (node (ref "C1") (pin "1") (pinfunction "1_1") (pintype "passive"))
      (node (ref "J4") (pin "21") (pinfunction "21_21") (pintype "passive"))
      (node (ref "R1") (pin "2") (pinfunction "2_2") (pintype "passive"))
    )
    (net (code "66") (name "SPN_POT_1_EXT") (class "Default")
      (node (ref "J4") (pin "19") (pinfunction "19_19") (pintype "passive"))
      (node (ref "R9") (pin "1") (pinfunction "1_1") (pintype "passive"))
    )
    (net (code "67") (name "SPN_POT_1_EXT_5V") (class "Default")
      (node (ref "R10") (pin "1") (pinfunction "1_1") (pintype "passive"))
      (node (ref "R22") (pin "1") (pinfunction "1_1") (pintype "passive"))
      (node (ref "R9") (pin "2") (pinfunction "2_2") (pintype "passive"))
    )
    (net (code "68") (name "SPN_POT_2") (class "Default")
      (node (ref "C8") (pin "1") (pinfunction "1_1") (pintype "passive"))
      (node (ref "J4") (pin "25") (pinfunction "25_25") (pintype "passive"))
      (node (ref "R26") (pin "2") (pinfunction "2_2") (pintype "passive"))
    )
    (net (code "69") (name "SPN_POT_2_EXT") (class "Default")
      (node (ref "J4") (pin "23") (pinfunction "23_23") (pintype "passive"))
      (node (ref "R4") (pin "1") (pinfunction "1_1") (pintype "passive"))
    )
    (net (code "70") (name "SPN_POT_2_EXT_5V") (class "Default")
      (node (ref "R23") (pin "1") (pinfunction "1_1") (pintype "passive"))
      (node (ref "R4") (pin "2") (pinfunction "2_2") (pintype "passive"))
      (node (ref "R6") (pin "1") (pinfunction "1_1") (pintype "passive"))
    )
    (net (code "71") (name "SPN_POT_3") (class "Default")
      (node (ref "C7") (pin "1") (pinfunction "1_1") (pintype "passive"))
      (node (ref "J4") (pin "29") (pinfunction "29_29") (pintype "passive"))
      (node (ref "R25") (pin "2") (pinfunction "2_2") (pintype "passive"))
    )
    (net (code "72") (name "SPN_POT_3_EXT") (class "Default")
      (node (ref "J4") (pin "27") (pinfunction "27_27") (pintype "passive"))
      (node (ref "R15") (pin "1") (pinfunction "1_1") (pintype "passive"))
    )
    (net (code "73") (name "SPN_POT_3_EXT_5V") (class "Default")
      (node (ref "R15") (pin "2") (pinfunction "2_2") (pintype "passive"))
      (node (ref "R16") (pin "1") (pinfunction "1_1") (pintype "passive"))
      (node (ref "R24") (pin "1") (pinfunction "1_1") (pintype "passive"))
    )
    (net (code "74") (name "SPN_POT_4") (class "Default")
      (node (ref "C4") (pin "1") (pinfunction "1_1") (pintype "passive"))
      (node (ref "J4") (pin "33") (pinfunction "33_33") (pintype "passive"))
      (node (ref "R5") (pin "2") (pinfunction "2_2") (pintype "passive"))
    )
    (net (code "75") (name "SPN_POT_4_EXT") (class "Default")
      (node (ref "J4") (pin "31") (pinfunction "31_31") (pintype "passive"))
      (node (ref "R17") (pin "1") (pinfunction "1_1") (pintype "passive"))
    )
    (net (code "76") (name "SPN_POT_4_EXT_5V") (class "Default")
      (node (ref "R17") (pin "2") (pinfunction "2_2") (pintype "passive"))
      (node (ref "R18") (pin "1") (pinfunction "1_1") (pintype "passive"))
      (node (ref "R19") (pin "1") (pinfunction "1_1") (pintype "passive"))
    )
    (net (code "77") (name "SPN_POT_5") (class "Default")
      (node (ref "C5") (pin "1") (pinfunction "1_1") (pintype "passive"))
      (node (ref "J4") (pin "37") (pinfunction "37_37") (pintype "passive"))
      (node (ref "R7") (pin "2") (pinfunction "2_2") (pintype "passive"))
    )
    (net (code "78") (name "SPN_POT_5_EXT") (class "Default")
      (node (ref "J4") (pin "35") (pinfunction "35_35") (pintype "passive"))
      (node (ref "R11") (pin "1") (pinfunction "1_1") (pintype "passive"))
    )
    (net (code "79") (name "SPN_POT_5_EXT_5V") (class "Default")
      (node (ref "R11") (pin "2") (pinfunction "2_2") (pintype "passive"))
      (node (ref "R12") (pin "1") (pinfunction "1_1") (pintype "passive"))
      (node (ref "R20") (pin "1") (pinfunction "1_1") (pintype "passive"))
    )
    (net (code "80") (name "SPN_POT_6") (class "Default")
      (node (ref "C6") (pin "1") (pinfunction "1_1") (pintype "passive"))
      (node (ref "J5") (pin "1") (pinfunction "1_1") (pintype "passive"))
      (node (ref "R8") (pin "2") (pinfunction "2_2") (pintype "passive"))
    )
    (net (code "81") (name "SPN_POT_6_EXT") (class "Default")
      (node (ref "J4") (pin "39") (pinfunction "39_39") (pintype "passive"))
      (node (ref "R13") (pin "1") (pinfunction "1_1") (pintype "passive"))
    )
    (net (code "82") (name "SPN_POT_6_EXT_5V") (class "Default")
      (node (ref "R13") (pin "2") (pinfunction "2_2") (pintype "passive"))
      (node (ref "R14") (pin "1") (pinfunction "1_1") (pintype "passive"))
      (node (ref "R21") (pin "1") (pinfunction "1_1") (pintype "passive"))
    )
    (net (code "83") (name "STEERING_1") (class "Default")
      (node (ref "J5") (pin "21") (pinfunction "21_21") (pintype "passive"))
      (node (ref "U20") (pin "5") (pinfunction "OUT_5") (pintype "output"))
    )
    (net (code "84") (name "STEERING_1_EXT") (class "Default")
      (node (ref "J5") (pin "19") (pinfunction "19_19") (pintype "passive"))
      (node (ref "U20") (pin "2") (pinfunction "IN_2") (pintype "input"))
    )
    (net (code "85") (name "STEERING_2") (class "Default")
      (node (ref "J5") (pin "25") (pinfunction "25_25") (pintype "passive"))
      (node (ref "U23") (pin "5") (pinfunction "OUT_5") (pintype "output"))
    )
    (net (code "86") (name "STEERING_2_EXT") (class "Default")
      (node (ref "J5") (pin "23") (pinfunction "23_23") (pintype "passive"))
      (node (ref "U23") (pin "2") (pinfunction "IN_2") (pintype "input"))
    )
    (net (code "87") (name "unconnected-(J4-Pad40)") (class "Default")
      (node (ref "J4") (pin "40") (pinfunction "40_40") (pintype "passive"))
    )
    (net (code "88") (name "unconnected-(J5-Pad39)") (class "Default")
      (node (ref "J5") (pin "39") (pinfunction "39_39") (pintype "passive"))
    )
    (net (code "89") (name "unconnected-(J5-Pad40)") (class "Default")
      (node (ref "J5") (pin "40") (pinfunction "40_40") (pintype "passive"))
    )
  )
)
